# esp32-nbiot-xx-v12-wroom32.net
KiCad netlist of a schematic drawn in EAGLE
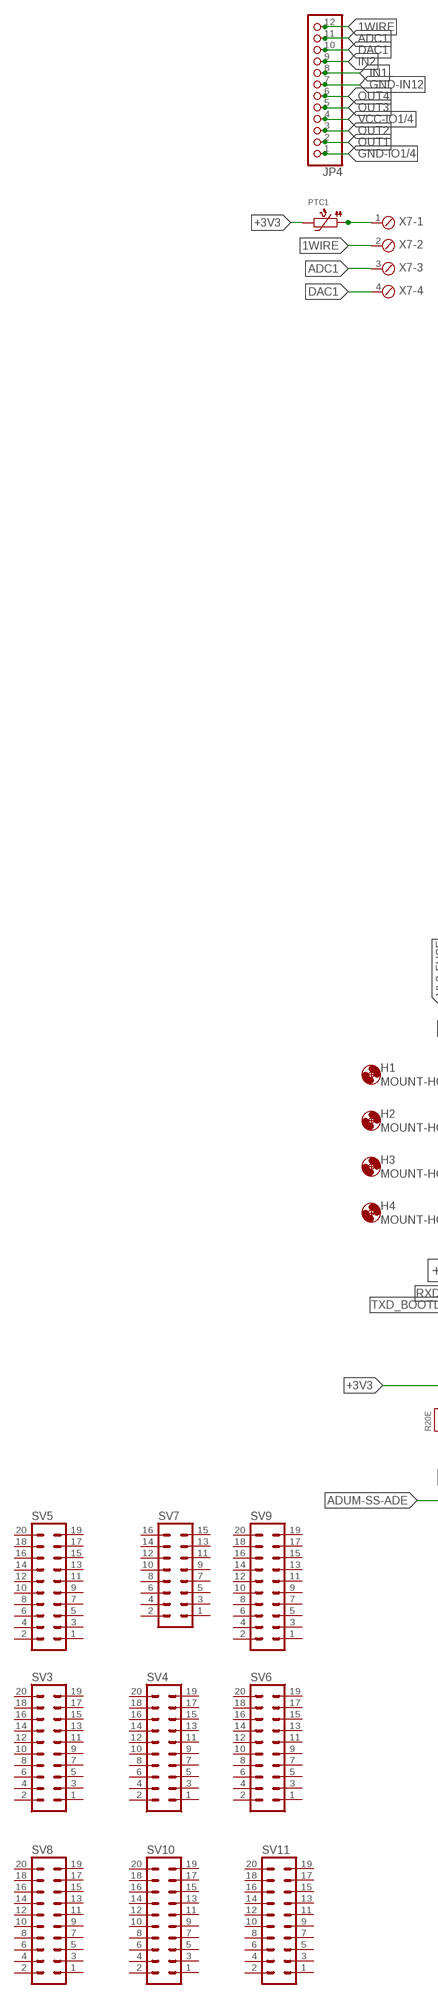
[diagram p0: schematic, sheet 1, part 1 of 3]
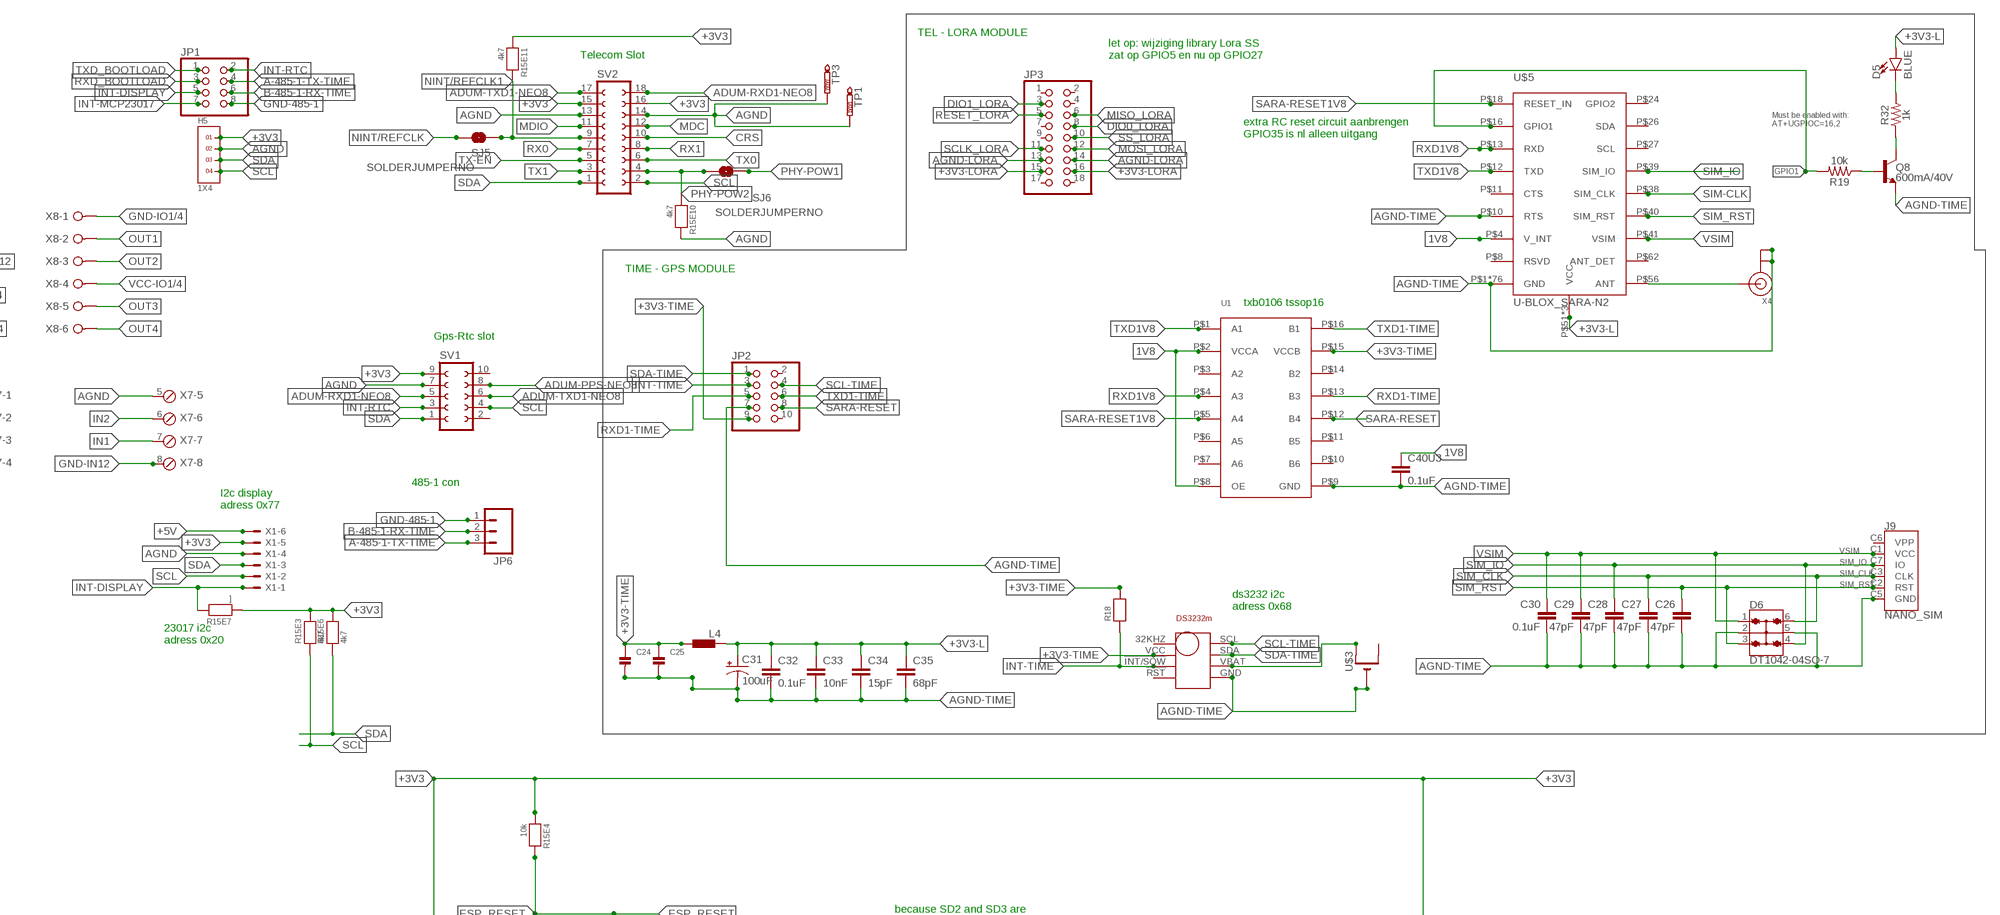
[diagram p1: schematic, sheet 1, part 2 of 3]
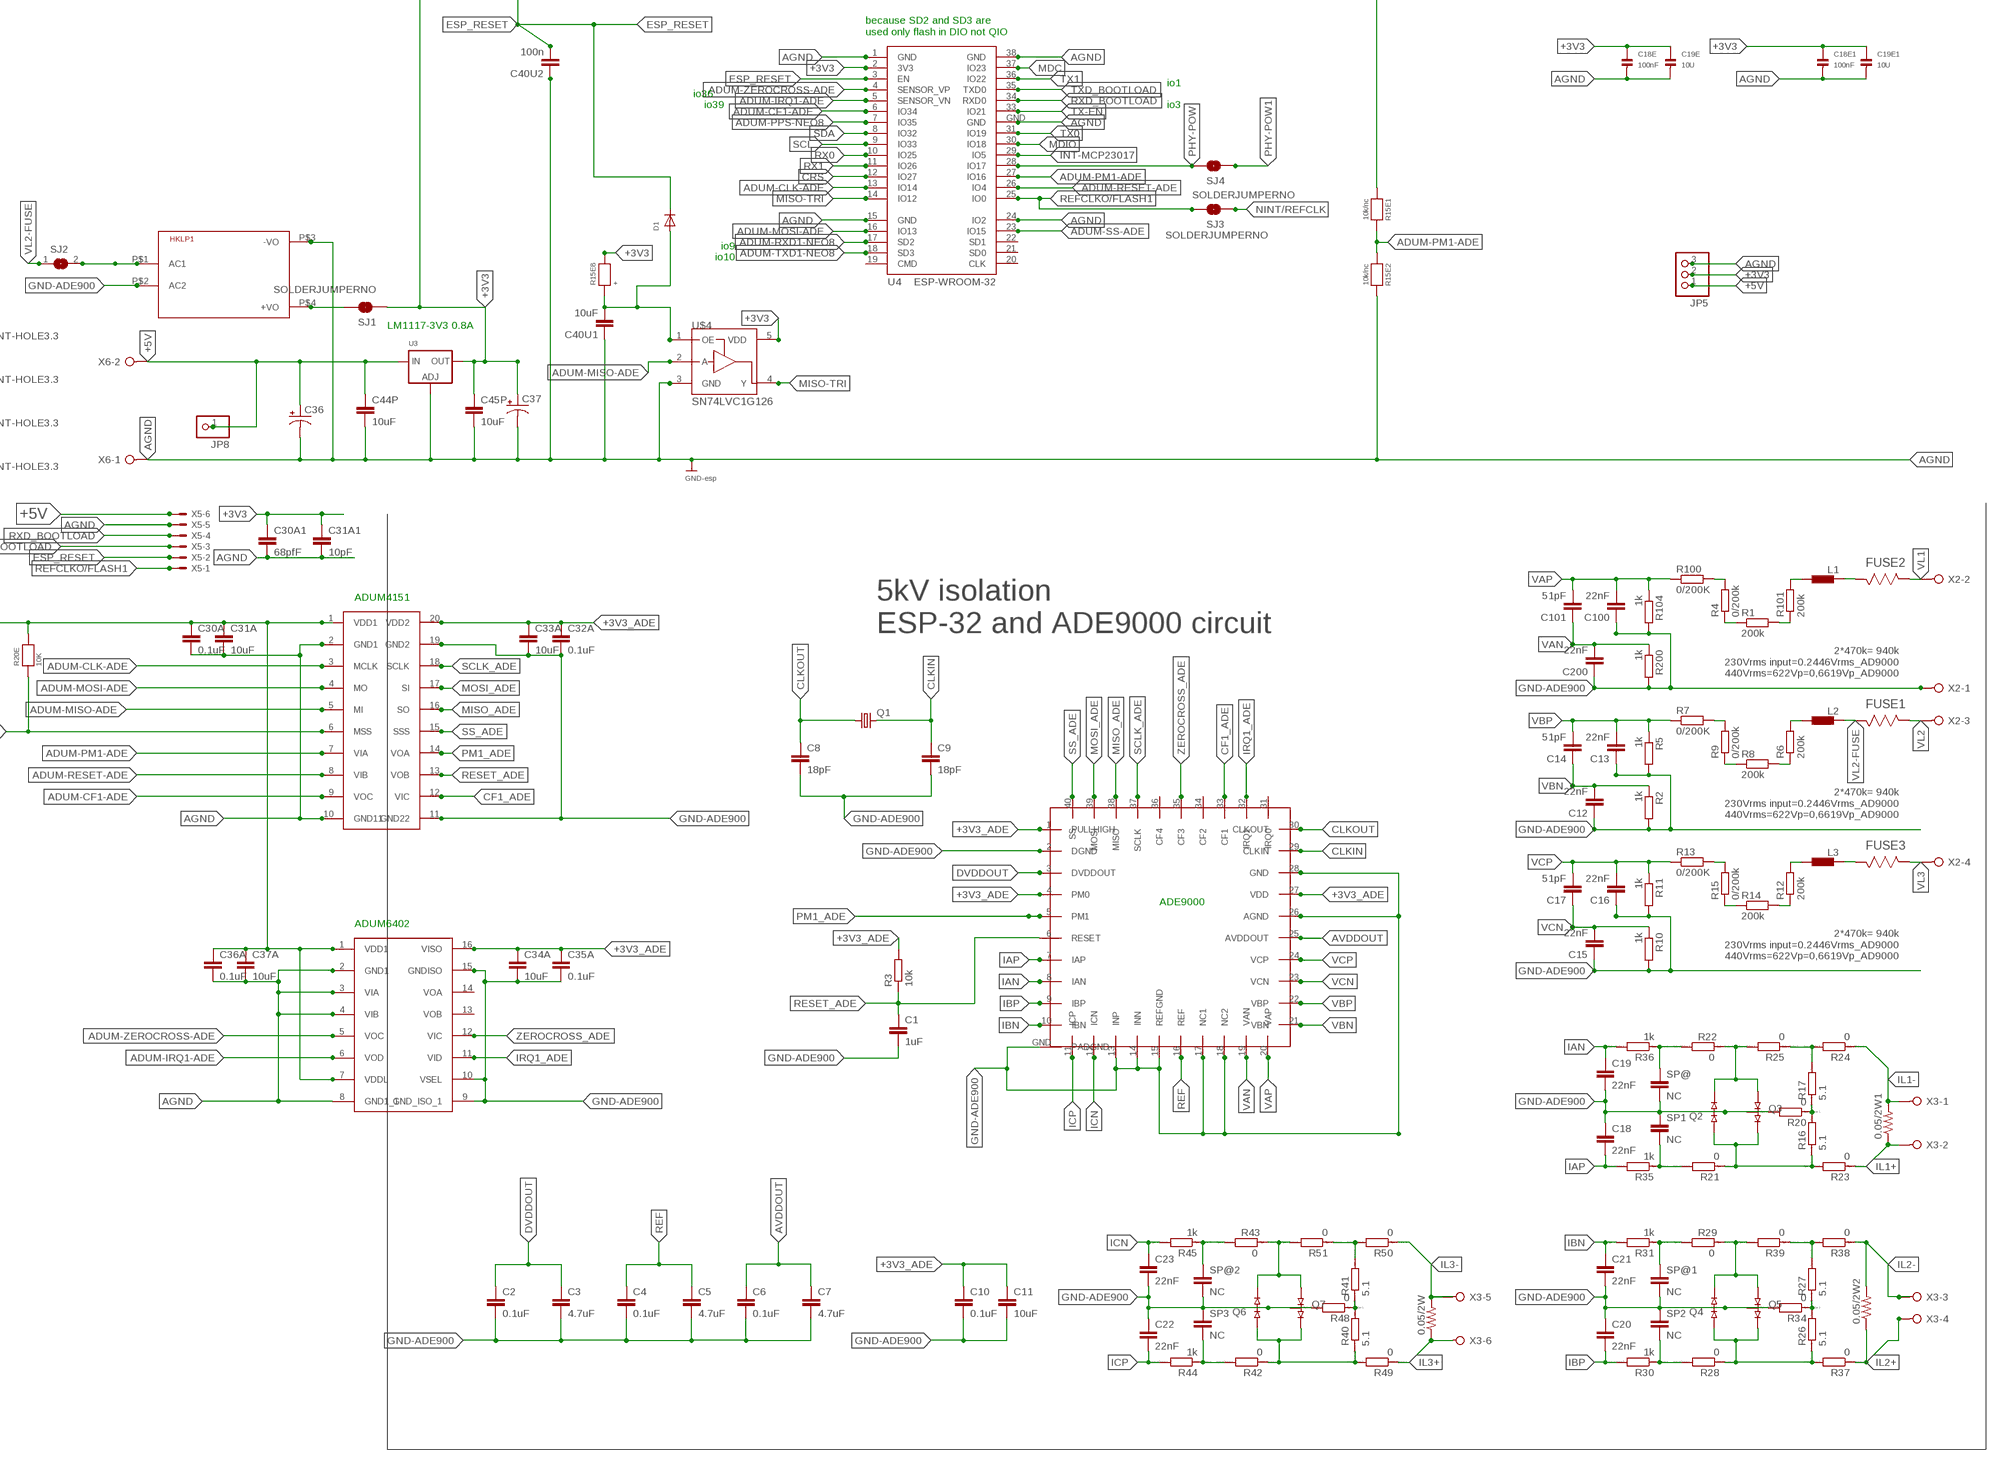
[diagram p2: schematic, sheet 1, part 3 of 3]

(export (version "E")
  (design (tool "Eeschema 10.0.6"))
  (components
    (comp (ref "0.05/2W")
      (value "R-US_R4527")
      (footprint "eagle-import:R4527")
      (libsource (lib "eagle-import") (part "R-US_R4527"))
    )
    (comp (ref "0.05/2W1")
      (value "R-US_R4527")
      (footprint "eagle-import:R4527")
      (libsource (lib "eagle-import") (part "R-US_R4527"))
    )
    (comp (ref "0.05/2W2")
      (value "R-US_R4527")
      (footprint "eagle-import:R4527")
      (libsource (lib "eagle-import") (part "R-US_R4527"))
    )
    (comp (ref "ADE9000")
      (value "ADE9000")
      (footprint "eagle-import:LFCSP40")
      (libsource (lib "eagle-import") (part "ADE9000"))
    )
    (comp (ref "ADUM4151")
      (value "ADUM4151")
      (footprint "eagle-import:SOIC20R")
      (libsource (lib "eagle-import") (part "ADUM4151"))
    )
    (comp (ref "ADUM6402-2")
      (value "ADUM6402")
      (footprint "eagle-import:SOIC16R")
      (libsource (lib "eagle-import") (part "ADUM6402"))
    )
    (comp (ref "C1")
      (value "1uF")
      (footprint "eagle-import:C0805")
      (libsource (lib "eagle-import") (part "C-EUC0805"))
    )
    (comp (ref "C2")
      (value "0.1uF")
      (footprint "eagle-import:C0805")
      (libsource (lib "eagle-import") (part "C-EUC0805"))
    )
    (comp (ref "C3")
      (value "4.7uF")
      (footprint "eagle-import:C0805")
      (libsource (lib "eagle-import") (part "C-EUC0805"))
    )
    (comp (ref "C4")
      (value "0.1uF")
      (footprint "eagle-import:C0805")
      (libsource (lib "eagle-import") (part "C-EUC0805"))
    )
    (comp (ref "C5")
      (value "4.7uF")
      (footprint "eagle-import:C0805")
      (libsource (lib "eagle-import") (part "C-EUC0805"))
    )
    (comp (ref "C6")
      (value "0.1uF")
      (footprint "eagle-import:C0805")
      (libsource (lib "eagle-import") (part "C-EUC0805"))
    )
    (comp (ref "C7")
      (value "4.7uF")
      (footprint "eagle-import:C0805")
      (libsource (lib "eagle-import") (part "C-EUC0805"))
    )
    (comp (ref "C8")
      (value "18pF")
      (footprint "eagle-import:C0805")
      (libsource (lib "eagle-import") (part "C-EUC0805"))
    )
    (comp (ref "C9")
      (value "18pF")
      (footprint "eagle-import:C0805")
      (libsource (lib "eagle-import") (part "C-EUC0805"))
    )
    (comp (ref "C10")
      (value "0.1uF")
      (footprint "eagle-import:C0805")
      (libsource (lib "eagle-import") (part "C-EUC0805"))
    )
    (comp (ref "C11")
      (value "10uF")
      (footprint "eagle-import:C0805")
      (libsource (lib "eagle-import") (part "C-EUC0805"))
    )
    (comp (ref "C12")
      (value "22nF")
      (footprint "eagle-import:C0805")
      (libsource (lib "eagle-import") (part "C-EUC0805"))
    )
    (comp (ref "C13")
      (value "22nF")
      (footprint "eagle-import:C0805")
      (libsource (lib "eagle-import") (part "C-EUC0805"))
    )
    (comp (ref "C14")
      (value "51pF")
      (footprint "eagle-import:C0805")
      (libsource (lib "eagle-import") (part "C-EUC0805"))
    )
    (comp (ref "C15")
      (value "22nF")
      (footprint "eagle-import:C0805")
      (libsource (lib "eagle-import") (part "C-EUC0805"))
    )
    (comp (ref "C16")
      (value "22nF")
      (footprint "eagle-import:C0805")
      (libsource (lib "eagle-import") (part "C-EUC0805"))
    )
    (comp (ref "C17")
      (value "51pF")
      (footprint "eagle-import:C0805")
      (libsource (lib "eagle-import") (part "C-EUC0805"))
    )
    (comp (ref "C18")
      (value "22nF")
      (footprint "eagle-import:C0805")
      (libsource (lib "eagle-import") (part "C-EUC0805"))
    )
    (comp (ref "C18E")
      (value "100nF")
      (footprint "eagle-import:_0805")
      (libsource (lib "eagle-import") (part "CAP_CERAMIC_0805"))
    )
    (comp (ref "C18E1")
      (value "100nF")
      (footprint "eagle-import:_0805")
      (libsource (lib "eagle-import") (part "CAP_CERAMIC_0805"))
    )
    (comp (ref "C19")
      (value "22nF")
      (footprint "eagle-import:C0805")
      (libsource (lib "eagle-import") (part "C-EUC0805"))
    )
    (comp (ref "C19E")
      (value "10U")
      (footprint "eagle-import:_0805")
      (libsource (lib "eagle-import") (part "CAP_CERAMIC_0805"))
    )
    (comp (ref "C19E1")
      (value "10U")
      (footprint "eagle-import:_0805")
      (libsource (lib "eagle-import") (part "CAP_CERAMIC_0805"))
    )
    (comp (ref "C20")
      (value "22nF")
      (footprint "eagle-import:C0805")
      (libsource (lib "eagle-import") (part "C-EUC0805"))
    )
    (comp (ref "C21")
      (value "22nF")
      (footprint "eagle-import:C0805")
      (libsource (lib "eagle-import") (part "C-EUC0805"))
    )
    (comp (ref "C22")
      (value "22nF")
      (footprint "eagle-import:C0805")
      (libsource (lib "eagle-import") (part "C-EUC0805"))
    )
    (comp (ref "C23")
      (value "22nF")
      (footprint "eagle-import:C0805")
      (libsource (lib "eagle-import") (part "C-EUC0805"))
    )
    (comp (ref "C24")
      (value "CAP_CERAMIC0805")
      (footprint "eagle-import:0805")
      (libsource (lib "eagle-import") (part "CAP_CERAMIC0805"))
    )
    (comp (ref "C25")
      (value "CAP_CERAMIC0805")
      (footprint "eagle-import:0805")
      (libsource (lib "eagle-import") (part "CAP_CERAMIC0805"))
    )
    (comp (ref "C26")
      (value "47pF")
      (footprint "eagle-import:0603")
      (libsource (lib "eagle-import") (part "47PF-0603-50V-5%"))
    )
    (comp (ref "C27")
      (value "47pF")
      (footprint "eagle-import:0603")
      (libsource (lib "eagle-import") (part "47PF-0603-50V-5%"))
    )
    (comp (ref "C28")
      (value "47pF")
      (footprint "eagle-import:0603")
      (libsource (lib "eagle-import") (part "47PF-0603-50V-5%"))
    )
    (comp (ref "C29")
      (value "47pF")
      (footprint "eagle-import:0603")
      (libsource (lib "eagle-import") (part "47PF-0603-50V-5%"))
    )
    (comp (ref "C30")
      (value "0.1uF")
      (footprint "eagle-import:0603")
      (libsource (lib "eagle-import") (part "0.1UF-0603-25V-(+80/-20%)"))
    )
    (comp (ref "C30A")
      (value "0.1uF")
      (footprint "eagle-import:C0805")
      (libsource (lib "eagle-import") (part "C-EUC0805"))
    )
    (comp (ref "C30A1")
      (value "68pfF")
      (footprint "eagle-import:C0805")
      (libsource (lib "eagle-import") (part "C-EUC0805"))
    )
    (comp (ref "C31")
      (value "100uF")
      (footprint "eagle-import:1206-POLAR")
      (libsource (lib "eagle-import") (part "100UF-POLAR-1206-6.3V-20%"))
    )
    (comp (ref "C31A")
      (value "10uF")
      (footprint "eagle-import:C0805")
      (libsource (lib "eagle-import") (part "C-EUC0805"))
    )
    (comp (ref "C31A1")
      (value "10pF")
      (footprint "eagle-import:C0805")
      (libsource (lib "eagle-import") (part "C-EUC0805"))
    )
    (comp (ref "C32")
      (value "0.1uF")
      (footprint "eagle-import:0603")
      (libsource (lib "eagle-import") (part "0.1UF-0603-25V-(+80/-20%)"))
    )
    (comp (ref "C32A")
      (value "0.1uF")
      (footprint "eagle-import:C0805")
      (libsource (lib "eagle-import") (part "C-EUC0805"))
    )
    (comp (ref "C33")
      (value "10nF")
      (footprint "eagle-import:0603")
      (libsource (lib "eagle-import") (part "10NF-0603-50V-10%"))
    )
    (comp (ref "C33A")
      (value "10uF")
      (footprint "eagle-import:C0805")
      (libsource (lib "eagle-import") (part "C-EUC0805"))
    )
    (comp (ref "C34")
      (value "15pF")
      (footprint "eagle-import:0603")
      (libsource (lib "eagle-import") (part "15PF-0603-50V-5%"))
    )
    (comp (ref "C34A")
      (value "10uF")
      (footprint "eagle-import:C0805")
      (libsource (lib "eagle-import") (part "C-EUC0805"))
    )
    (comp (ref "C35")
      (value "68pF")
      (footprint "eagle-import:0603")
      (libsource (lib "eagle-import") (part "68PF-0603-50V-5%"))
    )
    (comp (ref "C35A")
      (value "0.1uF")
      (footprint "eagle-import:C0805")
      (libsource (lib "eagle-import") (part "C-EUC0805"))
    )
    (comp (ref "C36")
      (value "CPOL-USD/7343-31R")
      (footprint "eagle-import:D_7343-31R")
      (libsource (lib "eagle-import") (part "CPOL-USD/7343-31R"))
    )
    (comp (ref "C36A")
      (value "0.1uF")
      (footprint "eagle-import:C0805")
      (libsource (lib "eagle-import") (part "C-EUC0805"))
    )
    (comp (ref "C37")
      (value "CPOL-USD/7343-31R")
      (footprint "eagle-import:D_7343-31R")
      (libsource (lib "eagle-import") (part "CPOL-USD/7343-31R"))
    )
    (comp (ref "C37A")
      (value "10uF")
      (footprint "eagle-import:C0805")
      (libsource (lib "eagle-import") (part "C-EUC0805"))
    )
    (comp (ref "C40U1")
      (value "10uF")
      (footprint "eagle-import:C0805")
      (libsource (lib "eagle-import") (part "C-EUC0805"))
    )
    (comp (ref "C40U2")
      (value "100n")
      (footprint "eagle-import:C0805")
      (libsource (lib "eagle-import") (part "C-EUC0805"))
    )
    (comp (ref "C40U3")
      (value "0.1uF")
      (footprint "eagle-import:C0805")
      (libsource (lib "eagle-import") (part "C-EUC0805"))
    )
    (comp (ref "C44P")
      (value "10uF")
      (footprint "eagle-import:C0805")
      (libsource (lib "eagle-import") (part "C-EUC0805"))
    )
    (comp (ref "C45P")
      (value "10uF")
      (footprint "eagle-import:C0805")
      (libsource (lib "eagle-import") (part "C-EUC0805"))
    )
    (comp (ref "C100")
      (value "22nF")
      (footprint "eagle-import:C0805")
      (libsource (lib "eagle-import") (part "C-EUC0805"))
    )
    (comp (ref "C101")
      (value "51pF")
      (footprint "eagle-import:C0805")
      (libsource (lib "eagle-import") (part "C-EUC0805"))
    )
    (comp (ref "C200")
      (value "22nF")
      (footprint "eagle-import:C0805")
      (libsource (lib "eagle-import") (part "C-EUC0805"))
    )
    (comp (ref "D1")
      (value "DIODE_SOD-123FL")
      (footprint "eagle-import:SOD-123FL")
      (libsource (lib "eagle-import") (part "DIODE_SOD-123FL"))
    )
    (comp (ref "D5")
      (value "BLUE")
      (footprint "eagle-import:LED-0603")
      (libsource (lib "eagle-import") (part "LED-BLUE0603"))
    )
    (comp (ref "D6")
      (value "DT1042-04SO-7")
      (footprint "eagle-import:SOT23-6L")
      (libsource (lib "eagle-import") (part "TVS_DIODE_ARRAY_4DT1042-04SO-7"))
    )
    (comp (ref "FUSE1")
      (value "CRCW25124R70JNEG")
      (footprint "eagle-import:RESC6332X71N")
      (fields (field (name "TOLERANCE") "±5%"))
      (libsource (lib "eagle-import") (part "CRCW25124R70JNEG"))
    )
    (comp (ref "FUSE2")
      (value "CRCW25124R70JNEG")
      (footprint "eagle-import:RESC6332X71N")
      (fields (field (name "TOLERANCE") "±5%"))
      (libsource (lib "eagle-import") (part "CRCW25124R70JNEG"))
    )
    (comp (ref "FUSE3")
      (value "CRCW25124R70JNEG")
      (footprint "eagle-import:RESC6332X71N")
      (fields (field (name "TOLERANCE") "±5%"))
      (libsource (lib "eagle-import") (part "CRCW25124R70JNEG"))
    )
    (comp (ref "H1")
      (value "MOUNT-HOLE3.3")
      (footprint "eagle-import:3,3")
      (libsource (lib "eagle-import") (part "MOUNT-HOLE3.3"))
    )
    (comp (ref "H2")
      (value "MOUNT-HOLE3.3")
      (footprint "eagle-import:3,3")
      (libsource (lib "eagle-import") (part "MOUNT-HOLE3.3"))
    )
    (comp (ref "H3")
      (value "MOUNT-HOLE3.3")
      (footprint "eagle-import:3,3")
      (libsource (lib "eagle-import") (part "MOUNT-HOLE3.3"))
    )
    (comp (ref "H4")
      (value "MOUNT-HOLE3.3")
      (footprint "eagle-import:3,3")
      (libsource (lib "eagle-import") (part "MOUNT-HOLE3.3"))
    )
    (comp (ref "H5")
      (value "1X4")
      (footprint "eagle-import:1X4")
      (libsource (lib "eagle-import") (part "1X4"))
    )
    (comp (ref "HKLP1")
      (value "HKLPM01")
      (footprint "eagle-import:HKLPM01")
      (libsource (lib "eagle-import") (part "HKLPM01"))
    )
    (comp (ref "J9")
      (value "NANO_SIM")
      (footprint "eagle-import:NANO_SIM_WURTH_693043020611")
      (libsource (lib "eagle-import") (part "NANO_SIMWURTH"))
    )
    (comp (ref "JP1")
      (value "PINHD-2X4")
      (footprint "eagle-import:2X04")
      (libsource (lib "eagle-import") (part "PINHD-2X4"))
    )
    (comp (ref "JP2")
      (value "PINHD-2X5/90")
      (footprint "eagle-import:2X05_90")
      (libsource (lib "eagle-import") (part "PINHD-2X5/90"))
    )
    (comp (ref "JP3")
      (value "PINHD-2X9/90")
      (footprint "eagle-import:2X09_90")
      (libsource (lib "eagle-import") (part "PINHD-2X9/90"))
    )
    (comp (ref "JP4")
      (value "PINHD-1X12")
      (footprint "eagle-import:1X12")
      (libsource (lib "eagle-import") (part "PINHD-1X12"))
    )
    (comp (ref "JP5")
      (value "PINHD-1X3")
      (footprint "eagle-import:1X03")
      (libsource (lib "eagle-import") (part "PINHD-1X3"))
    )
    (comp (ref "JP6")
      (value "M03SCREW")
      (footprint "eagle-import:SCREWTERMINAL-3.5MM-3")
      (libsource (lib "eagle-import") (part "M03SCREW"))
    )
    (comp (ref "JP8")
      (value "PINHD-1X1")
      (footprint "eagle-import:1X01")
      (libsource (lib "eagle-import") (part "PINHD-1X1"))
    )
    (comp (ref "L1")
      (value "1500")
      (footprint "eagle-import:M0805")
      (libsource (lib "eagle-import") (part "FERRITE_BEAD0805"))
    )
    (comp (ref "L2")
      (value "1500")
      (footprint "eagle-import:M0805")
      (libsource (lib "eagle-import") (part "FERRITE_BEAD0805"))
    )
    (comp (ref "L3")
      (value "1500")
      (footprint "eagle-import:M0805")
      (libsource (lib "eagle-import") (part "FERRITE_BEAD0805"))
    )
    (comp (ref "L4")
      (value "1500")
      (footprint "eagle-import:M0805")
      (libsource (lib "eagle-import") (part "FERRITE_BEAD0805"))
    )
    (comp (ref "PTC1")
      (value "PTC1206")
      (footprint "eagle-import:1206")
      (libsource (lib "eagle-import") (part "PTC1206"))
    )
    (comp (ref "Q1")
      (value "CRYSTALCTS406")
      (footprint "eagle-import:CTS406")
      (libsource (lib "eagle-import") (part "CRYSTALCTS406"))
    )
    (comp (ref "Q2")
      (value "MMBD4148SE")
      (footprint "eagle-import:SOT23-3")
      (libsource (lib "eagle-import") (part "DUAL_DIODE_SOT23-3"))
    )
    (comp (ref "Q3")
      (value "MMBD4148SE")
      (footprint "eagle-import:SOT23-3")
      (libsource (lib "eagle-import") (part "DUAL_DIODE_SOT23-3"))
    )
    (comp (ref "Q4")
      (value "MMBD4148SE")
      (footprint "eagle-import:SOT23-3")
      (libsource (lib "eagle-import") (part "DUAL_DIODE_SOT23-3"))
    )
    (comp (ref "Q5")
      (value "MMBD4148SE")
      (footprint "eagle-import:SOT23-3")
      (libsource (lib "eagle-import") (part "DUAL_DIODE_SOT23-3"))
    )
    (comp (ref "Q6")
      (value "MMBD4148SE")
      (footprint "eagle-import:SOT23-3")
      (libsource (lib "eagle-import") (part "DUAL_DIODE_SOT23-3"))
    )
    (comp (ref "Q7")
      (value "MMBD4148SE")
      (footprint "eagle-import:SOT23-3")
      (libsource (lib "eagle-import") (part "DUAL_DIODE_SOT23-3"))
    )
    (comp (ref "Q8")
      (value "600mA/40V")
      (footprint "eagle-import:SOT23-3")
      (libsource (lib "eagle-import") (part "TRANS_NPN-MMBT2222AL"))
    )
    (comp (ref "R1")
      (value "200k")
      (footprint "eagle-import:M1206")
      (libsource (lib "eagle-import") (part "R-EU_M1206"))
    )
    (comp (ref "R2")
      (value "1k")
      (footprint "eagle-import:M0805")
      (libsource (lib "eagle-import") (part "R-EU_M0805"))
    )
    (comp (ref "R3")
      (value "10k")
      (footprint "eagle-import:M0805")
      (libsource (lib "eagle-import") (part "R-EU_M0805"))
    )
    (comp (ref "R4")
      (value "0/200k")
      (footprint "eagle-import:M1206")
      (libsource (lib "eagle-import") (part "R-EU_M1206"))
    )
    (comp (ref "R5")
      (value "1k")
      (footprint "eagle-import:M0805")
      (libsource (lib "eagle-import") (part "R-EU_M0805"))
    )
    (comp (ref "R6")
      (value "200k")
      (footprint "eagle-import:M1206")
      (libsource (lib "eagle-import") (part "R-EU_M1206"))
    )
    (comp (ref "R7")
      (value "0/200K")
      (footprint "eagle-import:M1206")
      (libsource (lib "eagle-import") (part "R-EU_M1206"))
    )
    (comp (ref "R8")
      (value "200k")
      (footprint "eagle-import:M1206")
      (libsource (lib "eagle-import") (part "R-EU_M1206"))
    )
    (comp (ref "R9")
      (value "0/200k")
      (footprint "eagle-import:M1206")
      (libsource (lib "eagle-import") (part "R-EU_M1206"))
    )
    (comp (ref "R10")
      (value "1k")
      (footprint "eagle-import:M0805")
      (libsource (lib "eagle-import") (part "R-EU_M0805"))
    )
    (comp (ref "R11")
      (value "1k")
      (footprint "eagle-import:M0805")
      (libsource (lib "eagle-import") (part "R-EU_M0805"))
    )
    (comp (ref "R12")
      (value "200k")
      (footprint "eagle-import:M1206")
      (libsource (lib "eagle-import") (part "R-EU_M1206"))
    )
    (comp (ref "R13")
      (value "0/200K")
      (footprint "eagle-import:M1206")
      (libsource (lib "eagle-import") (part "R-EU_M1206"))
    )
    (comp (ref "R14")
      (value "200k")
      (footprint "eagle-import:M1206")
      (libsource (lib "eagle-import") (part "R-EU_M1206"))
    )
    (comp (ref "R15")
      (value "0/200k")
      (footprint "eagle-import:M1206")
      (libsource (lib "eagle-import") (part "R-EU_M1206"))
    )
    (comp (ref "R15E1")
      (value "10k/nc")
      (footprint "eagle-import:_0805")
      (libsource (lib "eagle-import") (part "RESISTOR_0805"))
    )
    (comp (ref "R15E2")
      (value "10k/nc")
      (footprint "eagle-import:_0805")
      (libsource (lib "eagle-import") (part "RESISTOR_0805"))
    )
    (comp (ref "R15E3")
      (value "4k7")
      (footprint "eagle-import:_0805")
      (libsource (lib "eagle-import") (part "RESISTOR_0805"))
    )
    (comp (ref "R15E4")
      (value "10k")
      (footprint "eagle-import:_0805")
      (libsource (lib "eagle-import") (part "RESISTOR_0805"))
    )
    (comp (ref "R15E6")
      (value "4k7")
      (footprint "eagle-import:_0805")
      (libsource (lib "eagle-import") (part "RESISTOR_0805"))
    )
    (comp (ref "R15E7")
      (value "]")
      (footprint "eagle-import:_0805")
      (libsource (lib "eagle-import") (part "RESISTOR_0805"))
    )
    (comp (ref "R15E8")
      (value "+")
      (footprint "eagle-import:_0805")
      (libsource (lib "eagle-import") (part "RESISTOR_0805"))
    )
    (comp (ref "R15E10")
      (value "4k7")
      (footprint "eagle-import:_0805")
      (libsource (lib "eagle-import") (part "RESISTOR_0805"))
    )
    (comp (ref "R15E11")
      (value "4k7")
      (footprint "eagle-import:_0805")
      (libsource (lib "eagle-import") (part "RESISTOR_0805"))
    )
    (comp (ref "R16")
      (value "5.1")
      (footprint "eagle-import:R0805")
      (description "RES, 5.1, 0W1, 0%1, 0805-SMT, ROHS")
      (fields (field (name "MANUFACTURER") " TE Connectivity Passive Product"))
      (libsource (lib "eagle-import") (part "R"))
    )
    (comp (ref "R17")
      (value "5.1")
      (footprint "eagle-import:R0805")
      (libsource (lib "eagle-import") (part "R"))
    )
    (comp (ref "R18")
      (value "RESISTOR0805")
      (footprint "eagle-import:0805")
      (libsource (lib "eagle-import") (part "RESISTOR0805"))
    )
    (comp (ref "R19")
      (value "10k")
      (footprint "eagle-import:0603")
      (libsource (lib "eagle-import") (part "10KOHM-0603-1/10W-1%"))
    )
    (comp (ref "R20")
      (value "0")
      (footprint "eagle-import:R0603")
      (libsource (lib "eagle-import") (part "RR0603"))
    )
    (comp (ref "R20E")
      (value "10K")
      (footprint "eagle-import:_0805")
      (libsource (lib "eagle-import") (part "RESISTOR_0805"))
    )
    (comp (ref "R21")
      (value "0")
      (footprint "eagle-import:R0603")
      (libsource (lib "eagle-import") (part "RR0603"))
    )
    (comp (ref "R22")
      (value "0")
      (footprint "eagle-import:R0603")
      (libsource (lib "eagle-import") (part "RR0603"))
    )
    (comp (ref "R23")
      (value "0")
      (footprint "eagle-import:R0603")
      (libsource (lib "eagle-import") (part "RR0603"))
    )
    (comp (ref "R24")
      (value "0")
      (footprint "eagle-import:R0603")
      (libsource (lib "eagle-import") (part "RR0603"))
    )
    (comp (ref "R25")
      (value "0")
      (footprint "eagle-import:R0603")
      (libsource (lib "eagle-import") (part "RR0603"))
    )
    (comp (ref "R26")
      (value "5.1")
      (footprint "eagle-import:R0805")
      (description "RES, 5.1, 0W1, 0%1, 0805-SMT, ROHS")
      (fields (field (name "MANUFACTURER") " TE Connectivity Passive Product"))
      (libsource (lib "eagle-import") (part "R"))
    )
    (comp (ref "R27")
      (value "5.1")
      (footprint "eagle-import:R0805")
      (libsource (lib "eagle-import") (part "R"))
    )
    (comp (ref "R28")
      (value "0")
      (footprint "eagle-import:R0603")
      (libsource (lib "eagle-import") (part "RR0603"))
    )
    (comp (ref "R29")
      (value "0")
      (footprint "eagle-import:R0603")
      (libsource (lib "eagle-import") (part "RR0603"))
    )
    (comp (ref "R30")
      (value "1k")
      (footprint "eagle-import:R0603")
      (libsource (lib "eagle-import") (part "RR0603"))
    )
    (comp (ref "R31")
      (value "1k")
      (footprint "eagle-import:R0603")
      (libsource (lib "eagle-import") (part "RR0603"))
    )
    (comp (ref "R32")
      (value "1k")
      (footprint "eagle-import:0603")
      (libsource (lib "eagle-import") (part "1KOHM-0603-1/10W-1%"))
    )
    (comp (ref "R34")
      (value "0")
      (footprint "eagle-import:R0603")
      (libsource (lib "eagle-import") (part "RR0603"))
    )
    (comp (ref "R35")
      (value "1k")
      (footprint "eagle-import:R0603")
      (libsource (lib "eagle-import") (part "RR0603"))
    )
    (comp (ref "R36")
      (value "1k")
      (footprint "eagle-import:R0603")
      (libsource (lib "eagle-import") (part "RR0603"))
    )
    (comp (ref "R37")
      (value "0")
      (footprint "eagle-import:R0603")
      (libsource (lib "eagle-import") (part "RR0603"))
    )
    (comp (ref "R38")
      (value "0")
      (footprint "eagle-import:R0603")
      (libsource (lib "eagle-import") (part "RR0603"))
    )
    (comp (ref "R39")
      (value "0")
      (footprint "eagle-import:R0603")
      (libsource (lib "eagle-import") (part "RR0603"))
    )
    (comp (ref "R40")
      (value "5.1")
      (footprint "eagle-import:R0805")
      (description "RES, 5.1, 0W1, 0%1, 0805-SMT, ROHS")
      (fields (field (name "MANUFACTURER") " TE Connectivity Passive Product"))
      (libsource (lib "eagle-import") (part "R"))
    )
    (comp (ref "R41")
      (value "5.1")
      (footprint "eagle-import:R0805")
      (libsource (lib "eagle-import") (part "R"))
    )
    (comp (ref "R42")
      (value "0")
      (footprint "eagle-import:R0603")
      (libsource (lib "eagle-import") (part "RR0603"))
    )
    (comp (ref "R43")
      (value "0")
      (footprint "eagle-import:R0603")
      (libsource (lib "eagle-import") (part "RR0603"))
    )
    (comp (ref "R44")
      (value "1k")
      (footprint "eagle-import:R0603")
      (libsource (lib "eagle-import") (part "RR0603"))
    )
    (comp (ref "R45")
      (value "1k")
      (footprint "eagle-import:R0603")
      (libsource (lib "eagle-import") (part "RR0603"))
    )
    (comp (ref "R48")
      (value "0")
      (footprint "eagle-import:R0603")
      (libsource (lib "eagle-import") (part "RR0603"))
    )
    (comp (ref "R49")
      (value "0")
      (footprint "eagle-import:R0603")
      (libsource (lib "eagle-import") (part "RR0603"))
    )
    (comp (ref "R50")
      (value "0")
      (footprint "eagle-import:R0603")
      (libsource (lib "eagle-import") (part "RR0603"))
    )
    (comp (ref "R51")
      (value "0")
      (footprint "eagle-import:R0603")
      (libsource (lib "eagle-import") (part "RR0603"))
    )
    (comp (ref "R100")
      (value "0/200K")
      (footprint "eagle-import:M1206")
      (libsource (lib "eagle-import") (part "R-EU_M1206"))
    )
    (comp (ref "R101")
      (value "200k")
      (footprint "eagle-import:M1206")
      (libsource (lib "eagle-import") (part "R-EU_M1206"))
    )
    (comp (ref "R104")
      (value "1k")
      (footprint "eagle-import:M0805")
      (libsource (lib "eagle-import") (part "R-EU_M0805"))
    )
    (comp (ref "R200")
      (value "1k")
      (footprint "eagle-import:M0805")
      (libsource (lib "eagle-import") (part "R-EU_M0805"))
    )
    (comp (ref "SJ1")
      (value "SOLDERJUMPERNO")
      (footprint "eagle-import:SJ_2S-NO")
      (libsource (lib "eagle-import") (part "SOLDERJUMPERNO"))
    )
    (comp (ref "SJ2")
      (value "SOLDERJUMPERWAVE")
      (footprint "eagle-import:SOLDERJUMPER_WAVE")
      (libsource (lib "eagle-import") (part "SOLDERJUMPERWAVE"))
    )
    (comp (ref "SJ3")
      (value "SOLDERJUMPERNO")
      (footprint "eagle-import:SJ_2S-NO")
      (libsource (lib "eagle-import") (part "SOLDERJUMPERNO"))
    )
    (comp (ref "SJ4")
      (value "SOLDERJUMPERNO")
      (footprint "eagle-import:SJ_2S-NO")
      (libsource (lib "eagle-import") (part "SOLDERJUMPERNO"))
    )
    (comp (ref "SJ5")
      (value "SOLDERJUMPERNO")
      (footprint "eagle-import:SJ_2S-NO")
      (libsource (lib "eagle-import") (part "SOLDERJUMPERNO"))
    )
    (comp (ref "SJ6")
      (value "SOLDERJUMPERNO")
      (footprint "eagle-import:SJ_2S-NO")
      (libsource (lib "eagle-import") (part "SOLDERJUMPERNO"))
    )
    (comp (ref "SP1")
      (value "NC")
      (footprint "eagle-import:C0805")
      (libsource (lib "eagle-import") (part "C-EUC0805"))
    )
    (comp (ref "SP2")
      (value "NC")
      (footprint "eagle-import:C0805")
      (libsource (lib "eagle-import") (part "C-EUC0805"))
    )
    (comp (ref "SP3")
      (value "NC")
      (footprint "eagle-import:C0805")
      (libsource (lib "eagle-import") (part "C-EUC0805"))
    )
    (comp (ref "SP@")
      (value "NC")
      (footprint "eagle-import:C0805")
      (libsource (lib "eagle-import") (part "C-EUC0805"))
    )
    (comp (ref "SP@1")
      (value "NC")
      (footprint "eagle-import:C0805")
      (libsource (lib "eagle-import") (part "C-EUC0805"))
    )
    (comp (ref "SP@2")
      (value "NC")
      (footprint "eagle-import:C0805")
      (libsource (lib "eagle-import") (part "C-EUC0805"))
    )
    (comp (ref "SV1")
      (value "FE05-2W")
      (footprint "eagle-import:FE05-2W")
      (libsource (lib "eagle-import") (part "FE05-2W"))
    )
    (comp (ref "SV2")
      (value "FE09-2W")
      (footprint "eagle-import:FE09-2W")
      (libsource (lib "eagle-import") (part "FE09-2W"))
    )
    (comp (ref "SV3")
      (value "MA10-2")
      (footprint "eagle-import:MA10-2")
      (libsource (lib "eagle-import") (part "MA10-2"))
    )
    (comp (ref "SV4")
      (value "MA10-2")
      (footprint "eagle-import:MA10-2")
      (libsource (lib "eagle-import") (part "MA10-2"))
    )
    (comp (ref "SV5")
      (value "MA10-2")
      (footprint "eagle-import:MA10-2")
      (libsource (lib "eagle-import") (part "MA10-2"))
    )
    (comp (ref "SV6")
      (value "MA10-2")
      (footprint "eagle-import:MA10-2")
      (libsource (lib "eagle-import") (part "MA10-2"))
    )
    (comp (ref "SV7")
      (value "MA08-2")
      (footprint "eagle-import:MA08-2")
      (libsource (lib "eagle-import") (part "MA08-2"))
    )
    (comp (ref "SV8")
      (value "MA10-2")
      (footprint "eagle-import:MA10-2")
      (libsource (lib "eagle-import") (part "MA10-2"))
    )
    (comp (ref "SV9")
      (value "MA10-2")
      (footprint "eagle-import:MA10-2")
      (libsource (lib "eagle-import") (part "MA10-2"))
    )
    (comp (ref "SV10")
      (value "MA10-2")
      (footprint "eagle-import:MA10-2")
      (libsource (lib "eagle-import") (part "MA10-2"))
    )
    (comp (ref "SV11")
      (value "MA10-2")
      (footprint "eagle-import:MA10-2")
      (libsource (lib "eagle-import") (part "MA10-2"))
    )
    (comp (ref "TP1")
      (value "PTR1TP08SQ")
      (footprint "eagle-import:TP08SQ")
      (libsource (lib "eagle-import") (part "PTR1TP08SQ"))
    )
    (comp (ref "TP3")
      (value "PTR1TP08SQ")
      (footprint "eagle-import:TP08SQ")
      (libsource (lib "eagle-import") (part "PTR1TP08SQ"))
    )
    (comp (ref "U$1")
      (value "DS3232M")
      (footprint "eagle-import:SOIC8")
      (libsource (lib "eagle-import") (part "DS3232M"))
    )
    (comp (ref "U$3")
      (value "CR1220SMT")
      (footprint "eagle-import:CR1220-SMD")
      (libsource (lib "eagle-import") (part "CR1220SMT"))
    )
    (comp (ref "U$4")
      (value "SN74LVC1G126DBVT")
      (footprint "eagle-import:SOT-23-5L")
      (fields (field (name "MF") "Texas Instruments"))
      (libsource (lib "eagle-import") (part "SN74LVC1G126DBVT"))
    )
    (comp (ref "U$5")
      (value "U-BLOX_SARA-N2")
      (footprint "eagle-import:SARA-N2")
      (libsource (lib "eagle-import") (part "U-BLOX_SARA-N2"))
    )
    (comp (ref "U1")
      (value "TXB0106")
      (footprint "eagle-import:TSSOP16")
      (fields (field (name "MF") "Texas Instruments"))
      (libsource (lib "eagle-import") (part "TXB0106"))
    )
    (comp (ref "U3")
      (value "LM1117SOT223-REFLOW")
      (footprint "eagle-import:SOT223-R")
      (libsource (lib "eagle-import") (part "LM1117SOT223-REFLOW"))
    )
    (comp (ref "U4")
      (value "ESP-WROOM-32")
      (footprint "eagle-import:ESP-WROOM-32")
      (libsource (lib "eagle-import") (part "ESP-WROOM-32"))
    )
    (comp (ref "X1")
      (value "22-23-2061")
      (footprint "eagle-import:22-23-2061")
      (fields (field (name "MF") "MOLEX"))
      (libsource (lib "eagle-import") (part "22-23-2061"))
    )
    (comp (ref "X2")
      (value "W237-04P")
      (footprint "eagle-import:W237-4P")
      (libsource (lib "eagle-import") (part "W237-04P"))
    )
    (comp (ref "X3")
      (value "W237-06P")
      (footprint "eagle-import:W237-6P")
      (libsource (lib "eagle-import") (part "W237-06P"))
    )
    (comp (ref "X4")
      (value "ANTENNA_U.FL")
      (footprint "eagle-import:U.FL")
      (libsource (lib "eagle-import") (part "ANTENNA_U.FL"))
    )
    (comp (ref "X5")
      (value "22-23-2061")
      (footprint "eagle-import:22-23-2061")
      (fields (field (name "MF") "MOLEX"))
      (libsource (lib "eagle-import") (part "22-23-2061"))
    )
    (comp (ref "X6")
      (value "W237-02P")
      (footprint "eagle-import:W237-132")
      (libsource (lib "eagle-import") (part "W237-02P"))
    )
    (comp (ref "X7")
      (value "MPT8")
      (footprint "eagle-import:8POL254")
      (libsource (lib "eagle-import") (part "MPT8"))
    )
    (comp (ref "X8")
      (value "W237-06P")
      (footprint "eagle-import:W237-6P")
      (libsource (lib "eagle-import") (part "W237-06P"))
    )
  )
  (nets
    (net (code "1") (name "+3V3") (class "Default")
      (node (ref "ADUM4151") (pin "1") (pinfunction "VDD1_1") (pintype "bidirectional"))
      (node (ref "ADUM6402-2") (pin "1") (pinfunction "VDD1_1") (pintype "bidirectional"))
      (node (ref "ADUM6402-2") (pin "7") (pinfunction "VDDL_7") (pintype "bidirectional"))
      (node (ref "C18E") (pin "1") (pinfunction "P$1_1") (pintype "passive"))
      (node (ref "C18E1") (pin "1") (pinfunction "P$1_1") (pintype "passive"))
      (node (ref "C19E") (pin "1") (pinfunction "P$1_1") (pintype "passive"))
      (node (ref "C19E1") (pin "1") (pinfunction "P$1_1") (pintype "passive"))
      (node (ref "C30A") (pin "1") (pinfunction "1_1") (pintype "passive"))
      (node (ref "C30A1") (pin "1") (pinfunction "1_1") (pintype "passive"))
      (node (ref "C31A") (pin "1") (pinfunction "1_1") (pintype "passive"))
      (node (ref "C31A1") (pin "1") (pinfunction "1_1") (pintype "passive"))
      (node (ref "C36A") (pin "1") (pinfunction "1_1") (pintype "passive"))
      (node (ref "C37") (pin "+") (pinfunction "+_+") (pintype "passive"))
      (node (ref "C37A") (pin "1") (pinfunction "1_1") (pintype "passive"))
      (node (ref "C45P") (pin "1") (pinfunction "1_1") (pintype "passive"))
      (node (ref "H5") (pin "1") (pinfunction "1_1") (pintype "bidirectional"))
      (node (ref "JP5") (pin "2") (pinfunction "2_2") (pintype "passive"))
      (node (ref "PTC1") (pin "2") (pinfunction "2_2") (pintype "passive"))
      (node (ref "R15E1") (pin "1") (pinfunction "1_1") (pintype "passive"))
      (node (ref "R15E11") (pin "1") (pinfunction "1_1") (pintype "passive"))
      (node (ref "R15E3") (pin "2") (pinfunction "2_2") (pintype "passive"))
      (node (ref "R15E4") (pin "1") (pinfunction "1_1") (pintype "passive"))
      (node (ref "R15E6") (pin "2") (pinfunction "2_2") (pintype "passive"))
      (node (ref "R15E7") (pin "1") (pinfunction "1_1") (pintype "passive"))
      (node (ref "R15E8") (pin "2") (pinfunction "2_2") (pintype "passive"))
      (node (ref "R20E") (pin "2") (pinfunction "2_2") (pintype "passive"))
      (node (ref "SJ1") (pin "1") (pinfunction "1_1") (pintype "passive"))
      (node (ref "SV1") (pin "9") (pinfunction "9_9") (pintype "passive"))
      (node (ref "SV2") (pin "15") (pinfunction "15_15") (pintype "passive"))
      (node (ref "SV2") (pin "16") (pinfunction "16_16") (pintype "passive"))
      (node (ref "U$4") (pin "5") (pinfunction "VDD_5") (pintype "bidirectional"))
      (node (ref "U3") (pin "2") (pinfunction "OUT_2") (pintype "passive"))
      (node (ref "U4") (pin "2") (pinfunction "3V3_2") (pintype "power_in"))
      (node (ref "X1") (pin "5") (pinfunction "S_5") (pintype "passive"))
    )
    (net (code "2") (name "+3V3-L") (class "Default")
      (node (ref "C31") (pin "1") (pinfunction "+_1") (pintype "passive"))
      (node (ref "C32") (pin "1") (pinfunction "1_1") (pintype "passive"))
      (node (ref "C33") (pin "1") (pinfunction "1_1") (pintype "passive"))
      (node (ref "C34") (pin "1") (pinfunction "1_1") (pintype "passive"))
      (node (ref "C35") (pin "1") (pinfunction "1_1") (pintype "passive"))
      (node (ref "D5") (pin "A") (pinfunction "A_A") (pintype "passive"))
      (node (ref "L4") (pin "1") (pinfunction "1_1") (pintype "passive"))
      (node (ref "U$5") (pin "P$51") (pinfunction "VCC_P$51") (pintype "power_in"))
      (node (ref "U$5") (pin "P$52") (pinfunction "VCC_P$52") (pintype "power_in"))
      (node (ref "U$5") (pin "P$53") (pinfunction "VCC_P$53") (pintype "power_in"))
    )
    (net (code "3") (name "+3V3-LORA") (class "Default")
      (node (ref "JP3") (pin "15") (pinfunction "15_15") (pintype "passive"))
      (node (ref "JP3") (pin "16") (pinfunction "16_16") (pintype "passive"))
    )
    (net (code "4") (name "+3V3-TIME") (class "Default")
      (node (ref "C24") (pin "1") (pinfunction "P$1_1") (pintype "passive"))
      (node (ref "C25") (pin "1") (pinfunction "P$1_1") (pintype "passive"))
      (node (ref "JP2") (pin "9") (pinfunction "9_9") (pintype "passive"))
      (node (ref "L4") (pin "2") (pinfunction "2_2") (pintype "passive"))
      (node (ref "R18") (pin "2") (pinfunction "2_2") (pintype "passive"))
      (node (ref "U$1") (pin "VCC") (pinfunction "VCC_VCC") (pintype "power_in"))
      (node (ref "U1") (pin "P$15") (pinfunction "VCCB_P$15") (pintype "bidirectional"))
    )
    (net (code "5") (name "+3V3_ADE") (class "Default")
      (node (ref "ADE9000") (pin "1") (pinfunction "PULLHIGH_1") (pintype "bidirectional"))
      (node (ref "ADE9000") (pin "27") (pinfunction "VDD_27") (pintype "bidirectional"))
      (node (ref "ADE9000") (pin "4") (pinfunction "PM0_4") (pintype "bidirectional"))
      (node (ref "ADUM4151") (pin "20") (pinfunction "VDD2_20") (pintype "bidirectional"))
      (node (ref "ADUM6402-2") (pin "16") (pinfunction "VISO_16") (pintype "bidirectional"))
      (node (ref "C10") (pin "1") (pinfunction "1_1") (pintype "passive"))
      (node (ref "C11") (pin "1") (pinfunction "1_1") (pintype "passive"))
      (node (ref "C32A") (pin "1") (pinfunction "1_1") (pintype "passive"))
      (node (ref "C33A") (pin "1") (pinfunction "1_1") (pintype "passive"))
      (node (ref "C34A") (pin "1") (pinfunction "1_1") (pintype "passive"))
      (node (ref "C35A") (pin "1") (pinfunction "1_1") (pintype "passive"))
      (node (ref "R3") (pin "2") (pinfunction "2_2") (pintype "passive"))
    )
    (net (code "6") (name "+5V") (class "Default")
      (node (ref "C36") (pin "+") (pinfunction "+_+") (pintype "passive"))
      (node (ref "C44P") (pin "1") (pinfunction "1_1") (pintype "passive"))
      (node (ref "JP5") (pin "1") (pinfunction "1_1") (pintype "passive"))
      (node (ref "JP8") (pin "1") (pinfunction "1_1") (pintype "passive"))
      (node (ref "U3") (pin "3") (pinfunction "IN_3") (pintype "input"))
      (node (ref "X1") (pin "6") (pinfunction "S_6") (pintype "passive"))
      (node (ref "X5") (pin "6") (pinfunction "S_6") (pintype "passive"))
      (node (ref "X6") (pin "2") (pinfunction "KL_2") (pintype "passive"))
    )
    (net (code "7") (name "1V8") (class "Default")
      (node (ref "C40U3") (pin "1") (pinfunction "1_1") (pintype "passive"))
      (node (ref "U$5") (pin "P$4") (pinfunction "V_INT_P$4") (pintype "bidirectional"))
      (node (ref "U1") (pin "P$2") (pinfunction "VCCA_P$2") (pintype "bidirectional"))
      (node (ref "U1") (pin "P$8") (pinfunction "OE_P$8") (pintype "bidirectional"))
    )
    (net (code "8") (name "1WIRE") (class "Default")
      (node (ref "JP4") (pin "12") (pinfunction "12_12") (pintype "passive"))
      (node (ref "X7") (pin "2") (pinfunction "1_2") (pintype "passive"))
    )
    (net (code "9") (name "A-485-1-TX-TIME") (class "Default")
      (node (ref "JP1") (pin "4") (pinfunction "4_4") (pintype "passive"))
      (node (ref "JP6") (pin "3") (pinfunction "3_3") (pintype "passive"))
    )
    (net (code "10") (name "ADC1") (class "Default")
      (node (ref "JP4") (pin "11") (pinfunction "11_11") (pintype "passive"))
      (node (ref "X7") (pin "3") (pinfunction "1_3") (pintype "passive"))
    )
    (net (code "11") (name "ADUM-CF1-ADE") (class "Default")
      (node (ref "ADUM4151") (pin "9") (pinfunction "VOC_9") (pintype "bidirectional"))
      (node (ref "U4") (pin "6") (pinfunction "IO34_6") (pintype "bidirectional"))
    )
    (net (code "12") (name "ADUM-CLK-ADE") (class "Default")
      (node (ref "ADUM4151") (pin "3") (pinfunction "MCLK_3") (pintype "bidirectional"))
      (node (ref "U4") (pin "13") (pinfunction "IO14_13") (pintype "bidirectional"))
    )
    (net (code "13") (name "ADUM-IRQ1-ADE") (class "Default")
      (node (ref "ADUM6402-2") (pin "6") (pinfunction "VOD_6") (pintype "bidirectional"))
      (node (ref "U4") (pin "5") (pinfunction "SENSOR_VN_5") (pintype "bidirectional"))
    )
    (net (code "14") (name "ADUM-MISO-ADE") (class "Default")
      (node (ref "ADUM4151") (pin "5") (pinfunction "MI_5") (pintype "bidirectional"))
      (node (ref "U$4") (pin "2") (pinfunction "A_2") (pintype "bidirectional"))
    )
    (net (code "15") (name "ADUM-MOSI-ADE") (class "Default")
      (node (ref "ADUM4151") (pin "4") (pinfunction "MO_4") (pintype "bidirectional"))
      (node (ref "U4") (pin "16") (pinfunction "IO13_16") (pintype "bidirectional"))
    )
    (net (code "16") (name "ADUM-PM1-ADE") (class "Default")
      (node (ref "ADUM4151") (pin "7") (pinfunction "VIA_7") (pintype "bidirectional"))
      (node (ref "R15E1") (pin "2") (pinfunction "2_2") (pintype "passive"))
      (node (ref "R15E2") (pin "1") (pinfunction "1_1") (pintype "passive"))
      (node (ref "U4") (pin "27") (pinfunction "IO16_27") (pintype "bidirectional"))
    )
    (net (code "17") (name "ADUM-PPS-NEO8") (class "Default")
      (node (ref "SV1") (pin "8") (pinfunction "8_8") (pintype "passive"))
      (node (ref "U4") (pin "7") (pinfunction "IO35_7") (pintype "bidirectional"))
    )
    (net (code "18") (name "ADUM-RESET-ADE") (class "Default")
      (node (ref "ADUM4151") (pin "8") (pinfunction "VIB_8") (pintype "bidirectional"))
      (node (ref "U4") (pin "26") (pinfunction "IO4_26") (pintype "bidirectional"))
    )
    (net (code "19") (name "ADUM-RXD1-NEO8") (class "Default")
      (node (ref "SV1") (pin "5") (pinfunction "5_5") (pintype "passive"))
      (node (ref "SV2") (pin "18") (pinfunction "18_18") (pintype "passive"))
      (node (ref "U4") (pin "17") (pinfunction "SD2_17") (pintype "bidirectional"))
    )
    (net (code "20") (name "ADUM-SS-ADE") (class "Default")
      (node (ref "ADUM4151") (pin "6") (pinfunction "MSS_6") (pintype "bidirectional"))
      (node (ref "R20E") (pin "1") (pinfunction "1_1") (pintype "passive"))
      (node (ref "U4") (pin "23") (pinfunction "IO15_23") (pintype "bidirectional"))
    )
    (net (code "21") (name "ADUM-TXD1-NEO8") (class "Default")
      (node (ref "SV1") (pin "6") (pinfunction "6_6") (pintype "passive"))
      (node (ref "SV2") (pin "17") (pinfunction "17_17") (pintype "passive"))
      (node (ref "U4") (pin "18") (pinfunction "SD3_18") (pintype "bidirectional"))
    )
    (net (code "22") (name "ADUM-ZEROCROSS-ADE") (class "Default")
      (node (ref "ADUM6402-2") (pin "5") (pinfunction "VOC_5") (pintype "bidirectional"))
      (node (ref "U4") (pin "4") (pinfunction "SENSOR_VP_4") (pintype "bidirectional"))
    )
    (net (code "23") (name "AGND") (class "Default")
      (node (ref "ADUM4151") (pin "10") (pinfunction "GND11_10") (pintype "bidirectional"))
      (node (ref "ADUM4151") (pin "2") (pinfunction "GND1_2") (pintype "bidirectional"))
      (node (ref "ADUM6402-2") (pin "2") (pinfunction "GND1_2") (pintype "bidirectional"))
      (node (ref "ADUM6402-2") (pin "3") (pinfunction "VIA_3") (pintype "bidirectional"))
      (node (ref "ADUM6402-2") (pin "4") (pinfunction "VIB_4") (pintype "bidirectional"))
      (node (ref "ADUM6402-2") (pin "8") (pinfunction "GND1_1_8") (pintype "bidirectional"))
      (node (ref "C18E") (pin "2") (pinfunction "P$2_2") (pintype "passive"))
      (node (ref "C18E1") (pin "2") (pinfunction "P$2_2") (pintype "passive"))
      (node (ref "C19E") (pin "2") (pinfunction "P$2_2") (pintype "passive"))
      (node (ref "C19E1") (pin "2") (pinfunction "P$2_2") (pintype "passive"))
      (node (ref "C30A") (pin "2") (pinfunction "2_2") (pintype "passive"))
      (node (ref "C30A1") (pin "2") (pinfunction "2_2") (pintype "passive"))
      (node (ref "C31A") (pin "2") (pinfunction "2_2") (pintype "passive"))
      (node (ref "C31A1") (pin "2") (pinfunction "2_2") (pintype "passive"))
      (node (ref "C36") (pin "-") (pinfunction "-_-") (pintype "passive"))
      (node (ref "C36A") (pin "2") (pinfunction "2_2") (pintype "passive"))
      (node (ref "C37") (pin "-") (pinfunction "-_-") (pintype "passive"))
      (node (ref "C37A") (pin "2") (pinfunction "2_2") (pintype "passive"))
      (node (ref "C40U1") (pin "1") (pinfunction "1_1") (pintype "passive"))
      (node (ref "C40U2") (pin "1") (pinfunction "1_1") (pintype "passive"))
      (node (ref "C44P") (pin "2") (pinfunction "2_2") (pintype "passive"))
      (node (ref "C45P") (pin "2") (pinfunction "2_2") (pintype "passive"))
      (node (ref "H5") (pin "2") (pinfunction "2_2") (pintype "bidirectional"))
      (node (ref "HKLP1") (pin "P$3") (pinfunction "-VO_P$3") (pintype "bidirectional"))
      (node (ref "JP5") (pin "3") (pinfunction "3_3") (pintype "passive"))
      (node (ref "R15E10") (pin "2") (pinfunction "2_2") (pintype "passive"))
      (node (ref "R15E2") (pin "2") (pinfunction "2_2") (pintype "passive"))
      (node (ref "SV1") (pin "7") (pinfunction "7_7") (pintype "passive"))
      (node (ref "SV2") (pin "13") (pinfunction "13_13") (pintype "passive"))
      (node (ref "SV2") (pin "14") (pinfunction "14_14") (pintype "passive"))
      (node (ref "TP1") (pin "TP") (pinfunction "TP_TP") (pintype "input"))
      (node (ref "TP3") (pin "TP") (pinfunction "TP_TP") (pintype "input"))
      (node (ref "U$4") (pin "3") (pinfunction "GND_3") (pintype "bidirectional"))
      (node (ref "U3") (pin "1") (pinfunction "ADJ_1") (pintype "input"))
      (node (ref "U4") (pin "1") (pinfunction "GND_1") (pintype "power_in"))
      (node (ref "U4") (pin "15") (pinfunction "GND_15") (pintype "power_in"))
      (node (ref "U4") (pin "24") (pinfunction "IO2_24") (pintype "bidirectional"))
      (node (ref "U4") (pin "38") (pinfunction "GND_38") (pintype "power_in"))
      (node (ref "U4") (pin "GND") (pinfunction "GND_GND") (pintype "power_in"))
      (node (ref "X1") (pin "4") (pinfunction "S_4") (pintype "passive"))
      (node (ref "X5") (pin "5") (pinfunction "S_5") (pintype "passive"))
      (node (ref "X6") (pin "1") (pinfunction "KL_1") (pintype "passive"))
      (node (ref "X7") (pin "5") (pinfunction "1_5") (pintype "passive"))
    )
    (net (code "24") (name "AGND-LORA") (class "Default")
      (node (ref "JP3") (pin "13") (pinfunction "13_13") (pintype "passive"))
      (node (ref "JP3") (pin "14") (pinfunction "14_14") (pintype "passive"))
    )
    (net (code "25") (name "AGND-TIME") (class "Default")
      (node (ref "C24") (pin "2") (pinfunction "P$2_2") (pintype "passive"))
      (node (ref "C25") (pin "2") (pinfunction "P$2_2") (pintype "passive"))
      (node (ref "C26") (pin "2") (pinfunction "2_2") (pintype "passive"))
      (node (ref "C27") (pin "2") (pinfunction "2_2") (pintype "passive"))
      (node (ref "C28") (pin "2") (pinfunction "2_2") (pintype "passive"))
      (node (ref "C29") (pin "2") (pinfunction "2_2") (pintype "passive"))
      (node (ref "C30") (pin "2") (pinfunction "2_2") (pintype "passive"))
      (node (ref "C31") (pin "2") (pinfunction "-_2") (pintype "passive"))
      (node (ref "C32") (pin "2") (pinfunction "2_2") (pintype "passive"))
      (node (ref "C33") (pin "2") (pinfunction "2_2") (pintype "passive"))
      (node (ref "C34") (pin "2") (pinfunction "2_2") (pintype "passive"))
      (node (ref "C35") (pin "2") (pinfunction "2_2") (pintype "passive"))
      (node (ref "C40U3") (pin "2") (pinfunction "2_2") (pintype "passive"))
      (node (ref "D6") (pin "2") (pinfunction "2_2") (pintype "bidirectional"))
      (node (ref "D6") (pin "5") (pinfunction "5_5") (pintype "bidirectional"))
      (node (ref "J9") (pin "C5") (pinfunction "GND_C5") (pintype "bidirectional"))
      (node (ref "JP2") (pin "7") (pinfunction "7_7") (pintype "passive"))
      (node (ref "Q8") (pin "2") (pinfunction "E_2") (pintype "passive"))
      (node (ref "U$1") (pin "GND") (pinfunction "GND_GND") (pintype "power_in"))
      (node (ref "U$3") (pin "-") (pinfunction "-_-") (pintype "passive"))
      (node (ref "U$5") (pin "P$1") (pinfunction "GND_P$1") (pintype "power_in"))
      (node (ref "U$5") (pin "P$10") (pinfunction "RTS_P$10") (pintype "input"))
      (node (ref "U$5") (pin "P$14") (pinfunction "GND_P$14") (pintype "power_in"))
      (node (ref "U$5") (pin "P$15") (pinfunction "GND_P$15") (pintype "power_in"))
      (node (ref "U$5") (pin "P$17") (pinfunction "GND_P$17") (pintype "power_in"))
      (node (ref "U$5") (pin "P$19") (pinfunction "GND_P$19") (pintype "power_in"))
      (node (ref "U$5") (pin "P$2") (pinfunction "GND_P$2") (pintype "power_in"))
      (node (ref "U$5") (pin "P$20") (pinfunction "GND_P$20") (pintype "power_in"))
      (node (ref "U$5") (pin "P$21") (pinfunction "GND_P$21") (pintype "power_in"))
      (node (ref "U$5") (pin "P$22") (pinfunction "GND_P$22") (pintype "power_in"))
      (node (ref "U$5") (pin "P$23") (pinfunction "GND_P$23") (pintype "power_in"))
      (node (ref "U$5") (pin "P$25") (pinfunction "GND_P$25") (pintype "power_in"))
      (node (ref "U$5") (pin "P$28") (pinfunction "GND_P$28") (pintype "power_in"))
      (node (ref "U$5") (pin "P$29") (pinfunction "GND_P$29") (pintype "power_in"))
      (node (ref "U$5") (pin "P$3") (pinfunction "GND_P$3") (pintype "power_in"))
      (node (ref "U$5") (pin "P$30") (pinfunction "GND_P$30") (pintype "power_in"))
      (node (ref "U$5") (pin "P$31") (pinfunction "GND_P$31") (pintype "power_in"))
      (node (ref "U$5") (pin "P$32") (pinfunction "GND_P$32") (pintype "power_in"))
      (node (ref "U$5") (pin "P$33") (pinfunction "GND_P$33") (pintype "power_in"))
      (node (ref "U$5") (pin "P$34") (pinfunction "GND_P$34") (pintype "power_in"))
      (node (ref "U$5") (pin "P$35") (pinfunction "GND_P$35") (pintype "power_in"))
      (node (ref "U$5") (pin "P$36") (pinfunction "GND_P$36") (pintype "power_in"))
      (node (ref "U$5") (pin "P$37") (pinfunction "GND_P$37") (pintype "power_in"))
      (node (ref "U$5") (pin "P$42") (pinfunction "GND_P$42") (pintype "power_in"))
      (node (ref "U$5") (pin "P$43") (pinfunction "GND_P$43") (pintype "power_in"))
      (node (ref "U$5") (pin "P$44") (pinfunction "GND_P$44") (pintype "power_in"))
      (node (ref "U$5") (pin "P$45") (pinfunction "GND_P$45") (pintype "power_in"))
      (node (ref "U$5") (pin "P$46") (pinfunction "GND_P$46") (pintype "power_in"))
      (node (ref "U$5") (pin "P$47") (pinfunction "GND_P$47") (pintype "power_in"))
      (node (ref "U$5") (pin "P$48") (pinfunction "GND_P$48") (pintype "power_in"))
      (node (ref "U$5") (pin "P$49") (pinfunction "GND_P$49") (pintype "power_in"))
      (node (ref "U$5") (pin "P$5") (pinfunction "GND_P$5") (pintype "power_in"))
      (node (ref "U$5") (pin "P$50") (pinfunction "GND_P$50") (pintype "power_in"))
      (node (ref "U$5") (pin "P$54") (pinfunction "GND_P$54") (pintype "power_in"))
      (node (ref "U$5") (pin "P$55") (pinfunction "GND_P$55") (pintype "power_in"))
      (node (ref "U$5") (pin "P$57") (pinfunction "GND_P$57") (pintype "power_in"))
      (node (ref "U$5") (pin "P$58") (pinfunction "GND_P$58") (pintype "power_in"))
      (node (ref "U$5") (pin "P$59") (pinfunction "GND_P$59") (pintype "power_in"))
      (node (ref "U$5") (pin "P$6") (pinfunction "GND_P$6") (pintype "power_in"))
      (node (ref "U$5") (pin "P$60") (pinfunction "GND_P$60") (pintype "power_in"))
      (node (ref "U$5") (pin "P$61") (pinfunction "GND_P$61") (pintype "power_in"))
      (node (ref "U$5") (pin "P$63") (pinfunction "GND_P$63") (pintype "power_in"))
      (node (ref "U$5") (pin "P$64") (pinfunction "GND_P$64") (pintype "power_in"))
      (node (ref "U$5") (pin "P$65") (pinfunction "GND_P$65") (pintype "power_in"))
      (node (ref "U$5") (pin "P$66") (pinfunction "GND_P$66") (pintype "power_in"))
      (node (ref "U$5") (pin "P$67") (pinfunction "GND_P$67") (pintype "power_in"))
      (node (ref "U$5") (pin "P$68") (pinfunction "GND_P$68") (pintype "power_in"))
      (node (ref "U$5") (pin "P$69") (pinfunction "GND_P$69") (pintype "power_in"))
      (node (ref "U$5") (pin "P$7") (pinfunction "GND_P$7") (pintype "power_in"))
      (node (ref "U$5") (pin "P$70") (pinfunction "GND_P$70") (pintype "power_in"))
      (node (ref "U$5") (pin "P$71") (pinfunction "GND_P$71") (pintype "power_in"))
      (node (ref "U$5") (pin "P$72") (pinfunction "GND_P$72") (pintype "power_in"))
      (node (ref "U$5") (pin "P$73") (pinfunction "GND_P$73") (pintype "power_in"))
      (node (ref "U$5") (pin "P$74") (pinfunction "GND_P$74") (pintype "power_in"))
      (node (ref "U$5") (pin "P$75") (pinfunction "GND_P$75") (pintype "power_in"))
      (node (ref "U$5") (pin "P$76") (pinfunction "GND_P$76") (pintype "power_in"))
      (node (ref "U$5") (pin "P$77") (pinfunction "GND_P$77") (pintype "power_in"))
      (node (ref "U$5") (pin "P$78") (pinfunction "GND_P$78") (pintype "power_in"))
      (node (ref "U$5") (pin "P$79") (pinfunction "GND_P$79") (pintype "power_in"))
      (node (ref "U$5") (pin "P$80") (pinfunction "GND_P$80") (pintype "power_in"))
      (node (ref "U$5") (pin "P$81") (pinfunction "GND_P$81") (pintype "power_in"))
      (node (ref "U$5") (pin "P$82") (pinfunction "GND_P$82") (pintype "power_in"))
      (node (ref "U$5") (pin "P$83") (pinfunction "GND_P$83") (pintype "power_in"))
      (node (ref "U$5") (pin "P$84") (pinfunction "GND_P$84") (pintype "power_in"))
      (node (ref "U$5") (pin "P$85") (pinfunction "GND_P$85") (pintype "power_in"))
      (node (ref "U$5") (pin "P$86") (pinfunction "GND_P$86") (pintype "power_in"))
      (node (ref "U$5") (pin "P$87") (pinfunction "GND_P$87") (pintype "power_in"))
      (node (ref "U$5") (pin "P$88") (pinfunction "GND_P$88") (pintype "power_in"))
      (node (ref "U$5") (pin "P$89") (pinfunction "GND_P$89") (pintype "power_in"))
      (node (ref "U$5") (pin "P$9") (pinfunction "GND_P$9") (pintype "power_in"))
      (node (ref "U$5") (pin "P$90") (pinfunction "GND_P$90") (pintype "power_in"))
      (node (ref "U$5") (pin "P$91") (pinfunction "GND_P$91") (pintype "power_in"))
      (node (ref "U$5") (pin "P$92") (pinfunction "GND_P$92") (pintype "power_in"))
      (node (ref "U$5") (pin "P$93") (pinfunction "GND_P$93") (pintype "power_in"))
      (node (ref "U$5") (pin "P$94") (pinfunction "GND_P$94") (pintype "power_in"))
      (node (ref "U$5") (pin "P$95") (pinfunction "GND_P$95") (pintype "power_in"))
      (node (ref "U$5") (pin "P$96") (pinfunction "GND_P$96") (pintype "power_in"))
      (node (ref "U1") (pin "P$9") (pinfunction "GND_P$9") (pintype "bidirectional"))
      (node (ref "X4") (pin "1") (pinfunction "GND_1") (pintype "passive"))
      (node (ref "X4") (pin "2") (pinfunction "GND_2") (pintype "passive"))
    )
    (net (code "26") (name "AVDDOUT") (class "Default")
      (node (ref "ADE9000") (pin "25") (pinfunction "AVDDOUT_25") (pintype "bidirectional"))
      (node (ref "C6") (pin "1") (pinfunction "1_1") (pintype "passive"))
      (node (ref "C7") (pin "1") (pinfunction "1_1") (pintype "passive"))
    )
    (net (code "27") (name "B-485-1-RX-TIME") (class "Default")
      (node (ref "JP1") (pin "6") (pinfunction "6_6") (pintype "passive"))
      (node (ref "JP6") (pin "2") (pinfunction "2_2") (pintype "passive"))
    )
    (net (code "28") (name "CF1_ADE") (class "Default")
      (node (ref "ADE9000") (pin "33") (pinfunction "CF1_33") (pintype "bidirectional"))
      (node (ref "ADUM4151") (pin "12") (pinfunction "VIC_12") (pintype "bidirectional"))
    )
    (net (code "29") (name "CLKIN") (class "Default")
      (node (ref "ADE9000") (pin "29") (pinfunction "CLKIN_29") (pintype "bidirectional"))
      (node (ref "C9") (pin "1") (pinfunction "1_1") (pintype "passive"))
      (node (ref "Q1") (pin "3") (pinfunction "2_3") (pintype "passive"))
    )
    (net (code "30") (name "CLKOUT") (class "Default")
      (node (ref "ADE9000") (pin "30") (pinfunction "CLKOUT_30") (pintype "bidirectional"))
      (node (ref "C8") (pin "1") (pinfunction "1_1") (pintype "passive"))
      (node (ref "Q1") (pin "1") (pinfunction "1_1") (pintype "passive"))
    )
    (net (code "31") (name "CRS") (class "Default")
      (node (ref "SV2") (pin "10") (pinfunction "10_10") (pintype "passive"))
      (node (ref "U4") (pin "12") (pinfunction "IO27_12") (pintype "bidirectional"))
    )
    (net (code "32") (name "DAC1") (class "Default")
      (node (ref "JP4") (pin "10") (pinfunction "10_10") (pintype "passive"))
      (node (ref "X7") (pin "4") (pinfunction "1_4") (pintype "passive"))
    )
    (net (code "33") (name "DIO0_LORA") (class "Default")
      (node (ref "JP3") (pin "8") (pinfunction "8_8") (pintype "passive"))
    )
    (net (code "34") (name "DIO1_LORA") (class "Default")
      (node (ref "JP3") (pin "3") (pinfunction "3_3") (pintype "passive"))
    )
    (net (code "35") (name "DVDDOUT") (class "Default")
      (node (ref "ADE9000") (pin "3") (pinfunction "DVDDOUT_3") (pintype "bidirectional"))
      (node (ref "C2") (pin "1") (pinfunction "1_1") (pintype "passive"))
      (node (ref "C3") (pin "1") (pinfunction "1_1") (pintype "passive"))
    )
    (net (code "36") (name "ESP_RESET") (class "Default")
      (node (ref "C40U2") (pin "2") (pinfunction "2_2") (pintype "passive"))
      (node (ref "D1") (pin "C") (pinfunction "C_C") (pintype "passive"))
      (node (ref "R15E4") (pin "2") (pinfunction "2_2") (pintype "passive"))
      (node (ref "U4") (pin "3") (pinfunction "EN_3") (pintype "input"))
      (node (ref "X5") (pin "2") (pinfunction "S_2") (pintype "passive"))
    )
    (net (code "37") (name "GND-485-1") (class "Default")
      (node (ref "JP1") (pin "8") (pinfunction "8_8") (pintype "passive"))
      (node (ref "JP6") (pin "1") (pinfunction "1_1") (pintype "passive"))
    )
    (net (code "38") (name "GND-ADE900") (class "Default")
      (node (ref "ADE9000") (pin "13") (pinfunction "INP_13") (pintype "bidirectional"))
      (node (ref "ADE9000") (pin "14") (pinfunction "INN_14") (pintype "bidirectional"))
      (node (ref "ADE9000") (pin "15") (pinfunction "REFGND_15") (pintype "bidirectional"))
      (node (ref "ADE9000") (pin "17") (pinfunction "NC1_17") (pintype "bidirectional"))
      (node (ref "ADE9000") (pin "18") (pinfunction "NC2_18") (pintype "bidirectional"))
      (node (ref "ADE9000") (pin "2") (pinfunction "DGND_2") (pintype "bidirectional"))
      (node (ref "ADE9000") (pin "26") (pinfunction "AGND_26") (pintype "bidirectional"))
      (node (ref "ADE9000") (pin "28") (pinfunction "GND_28") (pintype "bidirectional"))
      (node (ref "ADE9000") (pin "GND") (pinfunction "PADGND_GND") (pintype "bidirectional"))
      (node (ref "ADUM4151") (pin "11") (pinfunction "GND22_11") (pintype "bidirectional"))
      (node (ref "ADUM4151") (pin "19") (pinfunction "GND2_19") (pintype "bidirectional"))
      (node (ref "ADUM6402-2") (pin "10") (pinfunction "VSEL_10") (pintype "bidirectional"))
      (node (ref "ADUM6402-2") (pin "15") (pinfunction "GNDISO_15") (pintype "bidirectional"))
      (node (ref "ADUM6402-2") (pin "9") (pinfunction "GND_ISO_1_9") (pintype "bidirectional"))
      (node (ref "C1") (pin "2") (pinfunction "2_2") (pintype "passive"))
      (node (ref "C10") (pin "2") (pinfunction "2_2") (pintype "passive"))
      (node (ref "C100") (pin "1") (pinfunction "1_1") (pintype "passive"))
      (node (ref "C11") (pin "2") (pinfunction "2_2") (pintype "passive"))
      (node (ref "C12") (pin "1") (pinfunction "1_1") (pintype "passive"))
      (node (ref "C13") (pin "1") (pinfunction "1_1") (pintype "passive"))
      (node (ref "C15") (pin "1") (pinfunction "1_1") (pintype "passive"))
      (node (ref "C16") (pin "1") (pinfunction "1_1") (pintype "passive"))
      (node (ref "C18") (pin "1") (pinfunction "1_1") (pintype "passive"))
      (node (ref "C19") (pin "2") (pinfunction "2_2") (pintype "passive"))
      (node (ref "C2") (pin "2") (pinfunction "2_2") (pintype "passive"))
      (node (ref "C20") (pin "1") (pinfunction "1_1") (pintype "passive"))
      (node (ref "C200") (pin "1") (pinfunction "1_1") (pintype "passive"))
      (node (ref "C21") (pin "2") (pinfunction "2_2") (pintype "passive"))
      (node (ref "C22") (pin "1") (pinfunction "1_1") (pintype "passive"))
      (node (ref "C23") (pin "2") (pinfunction "2_2") (pintype "passive"))
      (node (ref "C3") (pin "2") (pinfunction "2_2") (pintype "passive"))
      (node (ref "C32A") (pin "2") (pinfunction "2_2") (pintype "passive"))
      (node (ref "C33A") (pin "2") (pinfunction "2_2") (pintype "passive"))
      (node (ref "C34A") (pin "2") (pinfunction "2_2") (pintype "passive"))
      (node (ref "C35A") (pin "2") (pinfunction "2_2") (pintype "passive"))
      (node (ref "C4") (pin "2") (pinfunction "2_2") (pintype "passive"))
      (node (ref "C5") (pin "2") (pinfunction "2_2") (pintype "passive"))
      (node (ref "C6") (pin "2") (pinfunction "2_2") (pintype "passive"))
      (node (ref "C7") (pin "2") (pinfunction "2_2") (pintype "passive"))
      (node (ref "C8") (pin "2") (pinfunction "2_2") (pintype "passive"))
      (node (ref "C9") (pin "2") (pinfunction "2_2") (pintype "passive"))
      (node (ref "HKLP1") (pin "P$2") (pinfunction "AC2_P$2") (pintype "bidirectional"))
      (node (ref "Q2") (pin "3") (pinfunction "3_3") (pintype "passive"))
      (node (ref "Q3") (pin "3") (pinfunction "3_3") (pintype "passive"))
      (node (ref "Q4") (pin "3") (pinfunction "3_3") (pintype "passive"))
      (node (ref "Q5") (pin "3") (pinfunction "3_3") (pintype "passive"))
      (node (ref "Q6") (pin "3") (pinfunction "3_3") (pintype "passive"))
      (node (ref "Q7") (pin "3") (pinfunction "3_3") (pintype "passive"))
      (node (ref "R10") (pin "2") (pinfunction "2_2") (pintype "passive"))
      (node (ref "R104") (pin "2") (pinfunction "2_2") (pintype "passive"))
      (node (ref "R11") (pin "2") (pinfunction "2_2") (pintype "passive"))
      (node (ref "R2") (pin "2") (pinfunction "2_2") (pintype "passive"))
      (node (ref "R20") (pin "2") (pinfunction "2_2") (pintype "passive"))
      (node (ref "R200") (pin "2") (pinfunction "2_2") (pintype "passive"))
      (node (ref "R34") (pin "2") (pinfunction "2_2") (pintype "passive"))
      (node (ref "R48") (pin "2") (pinfunction "2_2") (pintype "passive"))
      (node (ref "R5") (pin "2") (pinfunction "2_2") (pintype "passive"))
      (node (ref "SP1") (pin "1") (pinfunction "1_1") (pintype "passive"))
      (node (ref "SP2") (pin "1") (pinfunction "1_1") (pintype "passive"))
      (node (ref "SP3") (pin "1") (pinfunction "1_1") (pintype "passive"))
      (node (ref "SP@") (pin "2") (pinfunction "2_2") (pintype "passive"))
      (node (ref "SP@1") (pin "2") (pinfunction "2_2") (pintype "passive"))
      (node (ref "SP@2") (pin "2") (pinfunction "2_2") (pintype "passive"))
      (node (ref "X2") (pin "1") (pinfunction "KL_1") (pintype "passive"))
    )
    (net (code "39") (name "GND-IN12") (class "Default")
      (node (ref "JP4") (pin "7") (pinfunction "7_7") (pintype "passive"))
      (node (ref "X7") (pin "8") (pinfunction "1_8") (pintype "passive"))
    )
    (net (code "40") (name "GND-IO1{slash}4") (class "Default")
      (node (ref "JP4") (pin "1") (pinfunction "1_1") (pintype "passive"))
      (node (ref "X8") (pin "1") (pinfunction "KL_1") (pintype "passive"))
    )
    (net (code "41") (name "GPIO1") (class "Default")
      (node (ref "R19") (pin "2") (pinfunction "2_2") (pintype "passive"))
      (node (ref "U$5") (pin "P$16") (pinfunction "GPIO1_P$16") (pintype "bidirectional"))
    )
    (net (code "42") (name "IAN") (class "Default")
      (node (ref "ADE9000") (pin "8") (pinfunction "IAN_8") (pintype "bidirectional"))
      (node (ref "C19") (pin "1") (pinfunction "1_1") (pintype "passive"))
      (node (ref "R36") (pin "2") (pinfunction "2_2") (pintype "passive"))
    )
    (net (code "43") (name "IAP") (class "Default")
      (node (ref "ADE9000") (pin "7") (pinfunction "IAP_7") (pintype "bidirectional"))
      (node (ref "C18") (pin "2") (pinfunction "2_2") (pintype "passive"))
      (node (ref "R35") (pin "2") (pinfunction "2_2") (pintype "passive"))
    )
    (net (code "44") (name "IBN") (class "Default")
      (node (ref "ADE9000") (pin "10") (pinfunction "IBN_10") (pintype "bidirectional"))
      (node (ref "C21") (pin "1") (pinfunction "1_1") (pintype "passive"))
      (node (ref "R31") (pin "2") (pinfunction "2_2") (pintype "passive"))
    )
    (net (code "45") (name "IBP") (class "Default")
      (node (ref "ADE9000") (pin "9") (pinfunction "IBP_9") (pintype "bidirectional"))
      (node (ref "C20") (pin "2") (pinfunction "2_2") (pintype "passive"))
      (node (ref "R30") (pin "2") (pinfunction "2_2") (pintype "passive"))
    )
    (net (code "46") (name "ICN") (class "Default")
      (node (ref "ADE9000") (pin "12") (pinfunction "ICN_12") (pintype "bidirectional"))
      (node (ref "C23") (pin "1") (pinfunction "1_1") (pintype "passive"))
      (node (ref "R45") (pin "2") (pinfunction "2_2") (pintype "passive"))
    )
    (net (code "47") (name "ICP") (class "Default")
      (node (ref "ADE9000") (pin "11") (pinfunction "ICP_11") (pintype "bidirectional"))
      (node (ref "C22") (pin "2") (pinfunction "2_2") (pintype "passive"))
      (node (ref "R44") (pin "2") (pinfunction "2_2") (pintype "passive"))
    )
    (net (code "48") (name "IL1+") (class "Default")
      (node (ref "0.05/2W1") (pin "1") (pinfunction "1_1") (pintype "passive"))
      (node (ref "R23") (pin "1") (pinfunction "1_1") (pintype "passive"))
      (node (ref "X3") (pin "2") (pinfunction "KL_2") (pintype "passive"))
    )
    (net (code "49") (name "IL1-") (class "Default")
      (node (ref "0.05/2W1") (pin "2") (pinfunction "2_2") (pintype "passive"))
      (node (ref "R24") (pin "1") (pinfunction "1_1") (pintype "passive"))
      (node (ref "X3") (pin "1") (pinfunction "KL_1") (pintype "passive"))
    )
    (net (code "50") (name "IL2+") (class "Default")
      (node (ref "0.05/2W2") (pin "1") (pinfunction "1_1") (pintype "passive"))
      (node (ref "R37") (pin "1") (pinfunction "1_1") (pintype "passive"))
      (node (ref "X3") (pin "4") (pinfunction "KL_4") (pintype "passive"))
    )
    (net (code "51") (name "IL2-") (class "Default")
      (node (ref "0.05/2W2") (pin "2") (pinfunction "2_2") (pintype "passive"))
      (node (ref "R38") (pin "1") (pinfunction "1_1") (pintype "passive"))
      (node (ref "X3") (pin "3") (pinfunction "KL_3") (pintype "passive"))
    )
    (net (code "52") (name "IL3+") (class "Default")
      (node (ref "0.05/2W") (pin "1") (pinfunction "1_1") (pintype "passive"))
      (node (ref "R49") (pin "1") (pinfunction "1_1") (pintype "passive"))
      (node (ref "X3") (pin "6") (pinfunction "KL_6") (pintype "passive"))
    )
    (net (code "53") (name "IL3-") (class "Default")
      (node (ref "0.05/2W") (pin "2") (pinfunction "2_2") (pintype "passive"))
      (node (ref "R50") (pin "1") (pinfunction "1_1") (pintype "passive"))
      (node (ref "X3") (pin "5") (pinfunction "KL_5") (pintype "passive"))
    )
    (net (code "54") (name "IN1") (class "Default")
      (node (ref "JP4") (pin "8") (pinfunction "8_8") (pintype "passive"))
      (node (ref "X7") (pin "7") (pinfunction "1_7") (pintype "passive"))
    )
    (net (code "55") (name "IN2") (class "Default")
      (node (ref "JP4") (pin "9") (pinfunction "9_9") (pintype "passive"))
      (node (ref "X7") (pin "6") (pinfunction "1_6") (pintype "passive"))
    )
    (net (code "56") (name "INT-DISPLAY") (class "Default")
      (node (ref "JP1") (pin "5") (pinfunction "5_5") (pintype "passive"))
      (node (ref "R15E7") (pin "2") (pinfunction "2_2") (pintype "passive"))
      (node (ref "X1") (pin "1") (pinfunction "S_1") (pintype "passive"))
    )
    (net (code "57") (name "INT-MCP23017") (class "Default")
      (node (ref "JP1") (pin "7") (pinfunction "7_7") (pintype "passive"))
      (node (ref "U4") (pin "29") (pinfunction "IO5_29") (pintype "bidirectional"))
    )
    (net (code "58") (name "INT-RTC") (class "Default")
      (node (ref "JP1") (pin "2") (pinfunction "2_2") (pintype "passive"))
      (node (ref "SV1") (pin "3") (pinfunction "3_3") (pintype "passive"))
    )
    (net (code "59") (name "INT-TIME") (class "Default")
      (node (ref "JP2") (pin "3") (pinfunction "3_3") (pintype "passive"))
      (node (ref "R18") (pin "1") (pinfunction "1_1") (pintype "passive"))
      (node (ref "U$1") (pin "!INT/!!SQW") (pinfunction "~{INT/~SQW}_!INT/!!SQW") (pintype "bidirectional"))
    )
    (net (code "60") (name "IRQ1_ADE") (class "Default")
      (node (ref "ADE9000") (pin "32") (pinfunction "IRQ1_32") (pintype "bidirectional"))
      (node (ref "ADUM6402-2") (pin "11") (pinfunction "VID_11") (pintype "bidirectional"))
    )
    (net (code "61") (name "MDC") (class "Default")
      (node (ref "SV2") (pin "12") (pinfunction "12_12") (pintype "passive"))
      (node (ref "U4") (pin "37") (pinfunction "IO23_37") (pintype "bidirectional"))
    )
    (net (code "62") (name "MDIO") (class "Default")
      (node (ref "SV2") (pin "11") (pinfunction "11_11") (pintype "passive"))
      (node (ref "U4") (pin "30") (pinfunction "IO18_30") (pintype "bidirectional"))
    )
    (net (code "63") (name "MISO-TRI") (class "Default")
      (node (ref "U$4") (pin "4") (pinfunction "Y_4") (pintype "bidirectional"))
      (node (ref "U4") (pin "14") (pinfunction "IO12_14") (pintype "bidirectional"))
    )
    (net (code "64") (name "MISO_ADE") (class "Default")
      (node (ref "ADE9000") (pin "38") (pinfunction "MISO_38") (pintype "bidirectional"))
      (node (ref "ADUM4151") (pin "16") (pinfunction "SO_16") (pintype "bidirectional"))
    )
    (net (code "65") (name "MISO_LORA") (class "Default")
      (node (ref "JP3") (pin "6") (pinfunction "6_6") (pintype "passive"))
    )
    (net (code "66") (name "MOSI_ADE") (class "Default")
      (node (ref "ADE9000") (pin "39") (pinfunction "MOSI_39") (pintype "bidirectional"))
      (node (ref "ADUM4151") (pin "17") (pinfunction "SI_17") (pintype "bidirectional"))
    )
    (net (code "67") (name "MOSI_LORA") (class "Default")
      (node (ref "JP3") (pin "12") (pinfunction "12_12") (pintype "passive"))
    )
    (net (code "68") (name "NINT{slash}REFCLK") (class "Default")
      (node (ref "SJ3") (pin "1") (pinfunction "1_1") (pintype "passive"))
      (node (ref "SJ5") (pin "2") (pinfunction "2_2") (pintype "passive"))
    )
    (net (code "69") (name "NINT{slash}REFCLK1") (class "Default")
      (node (ref "R15E11") (pin "2") (pinfunction "2_2") (pintype "passive"))
      (node (ref "SJ5") (pin "1") (pinfunction "1_1") (pintype "passive"))
      (node (ref "SV2") (pin "9") (pinfunction "9_9") (pintype "passive"))
    )
    (net (code "70") (name "Net-(D5-PadC)") (class "Default")
      (node (ref "D5") (pin "C") (pinfunction "C_C") (pintype "passive"))
      (node (ref "R32") (pin "2") (pinfunction "2_2") (pintype "passive"))
    )
    (net (code "71") (name "Net-(FUSE2-Pad1)") (class "Default")
      (node (ref "FUSE2") (pin "1") (pinfunction "1_1") (pintype "passive"))
      (node (ref "L1") (pin "1") (pinfunction "1_1") (pintype "passive"))
    )
    (net (code "72") (name "Net-(FUSE3-Pad1)") (class "Default")
      (node (ref "FUSE3") (pin "1") (pinfunction "1_1") (pintype "passive"))
      (node (ref "L3") (pin "1") (pinfunction "1_1") (pintype "passive"))
    )
    (net (code "73") (name "Net-(HKLP1-+VO)") (class "Default")
      (node (ref "HKLP1") (pin "P$4") (pinfunction "+VO_P$4") (pintype "bidirectional"))
      (node (ref "SJ1") (pin "2") (pinfunction "2_2") (pintype "passive"))
    )
    (net (code "74") (name "Net-(HKLP1-AC1)") (class "Default")
      (node (ref "HKLP1") (pin "P$1") (pinfunction "AC1_P$1") (pintype "bidirectional"))
      (node (ref "SJ2") (pin "2") (pinfunction "2_2") (pintype "passive"))
    )
    (net (code "75") (name "Net-(L1-Pad2)") (class "Default")
      (node (ref "L1") (pin "2") (pinfunction "2_2") (pintype "passive"))
      (node (ref "R101") (pin "2") (pinfunction "2_2") (pintype "passive"))
    )
    (net (code "76") (name "Net-(L2-Pad2)") (class "Default")
      (node (ref "L2") (pin "2") (pinfunction "2_2") (pintype "passive"))
      (node (ref "R6") (pin "2") (pinfunction "2_2") (pintype "passive"))
    )
    (net (code "77") (name "Net-(L3-Pad2)") (class "Default")
      (node (ref "L3") (pin "2") (pinfunction "2_2") (pintype "passive"))
      (node (ref "R12") (pin "2") (pinfunction "2_2") (pintype "passive"))
    )
    (net (code "78") (name "Net-(PTC1-Pad1)") (class "Default")
      (node (ref "PTC1") (pin "1") (pinfunction "1_1") (pintype "passive"))
      (node (ref "X7") (pin "1") (pinfunction "1_1") (pintype "passive"))
    )
    (net (code "79") (name "Net-(Q2-Pad1)") (class "Default")
      (node (ref "Q2") (pin "1") (pinfunction "1_1") (pintype "passive"))
      (node (ref "Q3") (pin "2") (pinfunction "2_2") (pintype "passive"))
      (node (ref "R16") (pin "1") (pinfunction "1_1") (pintype "passive"))
      (node (ref "R21") (pin "1") (pinfunction "1_1") (pintype "passive"))
      (node (ref "R23") (pin "2") (pinfunction "2_2") (pintype "passive"))
    )
    (net (code "80") (name "Net-(Q2-Pad2)") (class "Default")
      (node (ref "Q2") (pin "2") (pinfunction "2_2") (pintype "passive"))
      (node (ref "Q3") (pin "1") (pinfunction "1_1") (pintype "passive"))
      (node (ref "R22") (pin "2") (pinfunction "2_2") (pintype "passive"))
      (node (ref "R25") (pin "2") (pinfunction "2_2") (pintype "passive"))
    )
    (net (code "81") (name "Net-(Q4-Pad1)") (class "Default")
      (node (ref "Q4") (pin "1") (pinfunction "1_1") (pintype "passive"))
      (node (ref "Q5") (pin "2") (pinfunction "2_2") (pintype "passive"))
      (node (ref "R26") (pin "1") (pinfunction "1_1") (pintype "passive"))
      (node (ref "R28") (pin "1") (pinfunction "1_1") (pintype "passive"))
      (node (ref "R37") (pin "2") (pinfunction "2_2") (pintype "passive"))
    )
    (net (code "82") (name "Net-(Q4-Pad2)") (class "Default")
      (node (ref "Q4") (pin "2") (pinfunction "2_2") (pintype "passive"))
      (node (ref "Q5") (pin "1") (pinfunction "1_1") (pintype "passive"))
      (node (ref "R29") (pin "2") (pinfunction "2_2") (pintype "passive"))
      (node (ref "R39") (pin "2") (pinfunction "2_2") (pintype "passive"))
    )
    (net (code "83") (name "Net-(Q6-Pad1)") (class "Default")
      (node (ref "Q6") (pin "1") (pinfunction "1_1") (pintype "passive"))
      (node (ref "Q7") (pin "2") (pinfunction "2_2") (pintype "passive"))
      (node (ref "R40") (pin "1") (pinfunction "1_1") (pintype "passive"))
      (node (ref "R42") (pin "1") (pinfunction "1_1") (pintype "passive"))
      (node (ref "R49") (pin "2") (pinfunction "2_2") (pintype "passive"))
    )
    (net (code "84") (name "Net-(Q6-Pad2)") (class "Default")
      (node (ref "Q6") (pin "2") (pinfunction "2_2") (pintype "passive"))
      (node (ref "Q7") (pin "1") (pinfunction "1_1") (pintype "passive"))
      (node (ref "R43") (pin "2") (pinfunction "2_2") (pintype "passive"))
      (node (ref "R51") (pin "2") (pinfunction "2_2") (pintype "passive"))
    )
    (net (code "85") (name "Net-(Q8-B)") (class "Default")
      (node (ref "Q8") (pin "1") (pinfunction "B_1") (pintype "passive"))
      (node (ref "R19") (pin "1") (pinfunction "1_1") (pintype "passive"))
    )
    (net (code "86") (name "Net-(Q8-C)") (class "Default")
      (node (ref "Q8") (pin "3") (pinfunction "C_3") (pintype "passive"))
      (node (ref "R32") (pin "1") (pinfunction "1_1") (pintype "passive"))
    )
    (net (code "87") (name "Net-(R1-Pad1)") (class "Default")
      (node (ref "R1") (pin "1") (pinfunction "1_1") (pintype "passive"))
      (node (ref "R4") (pin "1") (pinfunction "1_1") (pintype "passive"))
    )
    (net (code "88") (name "Net-(R1-Pad2)") (class "Default")
      (node (ref "R1") (pin "2") (pinfunction "2_2") (pintype "passive"))
      (node (ref "R101") (pin "1") (pinfunction "1_1") (pintype "passive"))
    )
    (net (code "89") (name "Net-(R6-Pad1)") (class "Default")
      (node (ref "R6") (pin "1") (pinfunction "1_1") (pintype "passive"))
      (node (ref "R8") (pin "2") (pinfunction "2_2") (pintype "passive"))
    )
    (net (code "90") (name "Net-(R7-Pad2)") (class "Default")
      (node (ref "R7") (pin "2") (pinfunction "2_2") (pintype "passive"))
      (node (ref "R9") (pin "2") (pinfunction "2_2") (pintype "passive"))
    )
    (net (code "91") (name "Net-(R8-Pad1)") (class "Default")
      (node (ref "R8") (pin "1") (pinfunction "1_1") (pintype "passive"))
      (node (ref "R9") (pin "1") (pinfunction "1_1") (pintype "passive"))
    )
    (net (code "92") (name "Net-(R12-Pad1)") (class "Default")
      (node (ref "R12") (pin "1") (pinfunction "1_1") (pintype "passive"))
      (node (ref "R14") (pin "2") (pinfunction "2_2") (pintype "passive"))
    )
    (net (code "93") (name "Net-(R13-Pad2)") (class "Default")
      (node (ref "R13") (pin "2") (pinfunction "2_2") (pintype "passive"))
      (node (ref "R15") (pin "2") (pinfunction "2_2") (pintype "passive"))
    )
    (net (code "94") (name "Net-(R14-Pad1)") (class "Default")
      (node (ref "R14") (pin "1") (pinfunction "1_1") (pintype "passive"))
      (node (ref "R15") (pin "1") (pinfunction "1_1") (pintype "passive"))
    )
    (net (code "95") (name "Net-(R16-Pad2)") (class "Default")
      (node (ref "R16") (pin "2") (pinfunction "2_2") (pintype "passive"))
      (node (ref "R17") (pin "1") (pinfunction "1_1") (pintype "passive"))
      (node (ref "R20") (pin "1") (pinfunction "1_1") (pintype "passive"))
    )
    (net (code "96") (name "Net-(R17-Pad2)") (class "Default")
      (node (ref "R17") (pin "2") (pinfunction "2_2") (pintype "passive"))
      (node (ref "R24") (pin "2") (pinfunction "2_2") (pintype "passive"))
      (node (ref "R25") (pin "1") (pinfunction "1_1") (pintype "passive"))
    )
    (net (code "97") (name "Net-(R21-Pad2)") (class "Default")
      (node (ref "R21") (pin "2") (pinfunction "2_2") (pintype "passive"))
      (node (ref "R35") (pin "1") (pinfunction "1_1") (pintype "passive"))
      (node (ref "SP1") (pin "2") (pinfunction "2_2") (pintype "passive"))
    )
    (net (code "98") (name "Net-(R22-Pad1)") (class "Default")
      (node (ref "R22") (pin "1") (pinfunction "1_1") (pintype "passive"))
      (node (ref "R36") (pin "1") (pinfunction "1_1") (pintype "passive"))
      (node (ref "SP@") (pin "1") (pinfunction "1_1") (pintype "passive"))
    )
    (net (code "99") (name "Net-(R26-Pad2)") (class "Default")
      (node (ref "R26") (pin "2") (pinfunction "2_2") (pintype "passive"))
      (node (ref "R27") (pin "1") (pinfunction "1_1") (pintype "passive"))
      (node (ref "R34") (pin "1") (pinfunction "1_1") (pintype "passive"))
    )
    (net (code "100") (name "Net-(R27-Pad2)") (class "Default")
      (node (ref "R27") (pin "2") (pinfunction "2_2") (pintype "passive"))
      (node (ref "R38") (pin "2") (pinfunction "2_2") (pintype "passive"))
      (node (ref "R39") (pin "1") (pinfunction "1_1") (pintype "passive"))
    )
    (net (code "101") (name "Net-(R28-Pad2)") (class "Default")
      (node (ref "R28") (pin "2") (pinfunction "2_2") (pintype "passive"))
      (node (ref "R30") (pin "1") (pinfunction "1_1") (pintype "passive"))
      (node (ref "SP2") (pin "2") (pinfunction "2_2") (pintype "passive"))
    )
    (net (code "102") (name "Net-(R29-Pad1)") (class "Default")
      (node (ref "R29") (pin "1") (pinfunction "1_1") (pintype "passive"))
      (node (ref "R31") (pin "1") (pinfunction "1_1") (pintype "passive"))
      (node (ref "SP@1") (pin "1") (pinfunction "1_1") (pintype "passive"))
    )
    (net (code "103") (name "Net-(R40-Pad2)") (class "Default")
      (node (ref "R40") (pin "2") (pinfunction "2_2") (pintype "passive"))
      (node (ref "R41") (pin "1") (pinfunction "1_1") (pintype "passive"))
      (node (ref "R48") (pin "1") (pinfunction "1_1") (pintype "passive"))
    )
    (net (code "104") (name "Net-(R41-Pad2)") (class "Default")
      (node (ref "R41") (pin "2") (pinfunction "2_2") (pintype "passive"))
      (node (ref "R50") (pin "2") (pinfunction "2_2") (pintype "passive"))
      (node (ref "R51") (pin "1") (pinfunction "1_1") (pintype "passive"))
    )
    (net (code "105") (name "Net-(R42-Pad2)") (class "Default")
      (node (ref "R42") (pin "2") (pinfunction "2_2") (pintype "passive"))
      (node (ref "R44") (pin "1") (pinfunction "1_1") (pintype "passive"))
      (node (ref "SP3") (pin "2") (pinfunction "2_2") (pintype "passive"))
    )
    (net (code "106") (name "Net-(R43-Pad1)") (class "Default")
      (node (ref "R43") (pin "1") (pinfunction "1_1") (pintype "passive"))
      (node (ref "R45") (pin "1") (pinfunction "1_1") (pintype "passive"))
      (node (ref "SP@2") (pin "1") (pinfunction "1_1") (pintype "passive"))
    )
    (net (code "107") (name "Net-(R100-Pad2)") (class "Default")
      (node (ref "R100") (pin "2") (pinfunction "2_2") (pintype "passive"))
      (node (ref "R4") (pin "2") (pinfunction "2_2") (pintype "passive"))
    )
    (net (code "108") (name "Net-(U$3-+)") (class "Default")
      (node (ref "U$1") (pin "VBAT") (pinfunction "VBAT_VBAT") (pintype "power_in"))
      (node (ref "U$3") (pin "+$1") (pinfunction "+_+$1") (pintype "passive"))
    )
    (net (code "109") (name "Net-(U$4-OE)") (class "Default")
      (node (ref "C40U1") (pin "2") (pinfunction "2_2") (pintype "passive"))
      (node (ref "D1") (pin "A") (pinfunction "A_A") (pintype "passive"))
      (node (ref "R15E8") (pin "1") (pinfunction "1_1") (pintype "passive"))
      (node (ref "U$4") (pin "1") (pinfunction "OE_1") (pintype "bidirectional"))
    )
    (net (code "110") (name "Net-(U$5-ANT)") (class "Default")
      (node (ref "U$5") (pin "P$56") (pinfunction "ANT_P$56") (pintype "bidirectional"))
      (node (ref "X4") (pin "3") (pinfunction "SIGNAL_3") (pintype "passive"))
    )
    (net (code "111") (name "OUT1") (class "Default")
      (node (ref "JP4") (pin "2") (pinfunction "2_2") (pintype "passive"))
      (node (ref "X8") (pin "2") (pinfunction "KL_2") (pintype "passive"))
    )
    (net (code "112") (name "OUT2") (class "Default")
      (node (ref "JP4") (pin "3") (pinfunction "3_3") (pintype "passive"))
      (node (ref "X8") (pin "3") (pinfunction "KL_3") (pintype "passive"))
    )
    (net (code "113") (name "OUT3") (class "Default")
      (node (ref "JP4") (pin "5") (pinfunction "5_5") (pintype "passive"))
      (node (ref "X8") (pin "5") (pinfunction "KL_5") (pintype "passive"))
    )
    (net (code "114") (name "OUT4") (class "Default")
      (node (ref "JP4") (pin "6") (pinfunction "6_6") (pintype "passive"))
      (node (ref "X8") (pin "6") (pinfunction "KL_6") (pintype "passive"))
    )
    (net (code "115") (name "PHY-POW") (class "Default")
      (node (ref "SJ4") (pin "2") (pinfunction "2_2") (pintype "passive"))
      (node (ref "U4") (pin "28") (pinfunction "IO17_28") (pintype "bidirectional"))
    )
    (net (code "116") (name "PHY-POW1") (class "Default")
      (node (ref "SJ4") (pin "1") (pinfunction "1_1") (pintype "passive"))
      (node (ref "SJ6") (pin "1") (pinfunction "1_1") (pintype "passive"))
    )
    (net (code "117") (name "PHY-POW2") (class "Default")
      (node (ref "R15E10") (pin "1") (pinfunction "1_1") (pintype "passive"))
      (node (ref "SJ6") (pin "2") (pinfunction "2_2") (pintype "passive"))
      (node (ref "SV2") (pin "4") (pinfunction "4_4") (pintype "passive"))
    )
    (net (code "118") (name "PM1_ADE") (class "Default")
      (node (ref "ADE9000") (pin "5") (pinfunction "PM1_5") (pintype "bidirectional"))
      (node (ref "ADUM4151") (pin "14") (pinfunction "VOA_14") (pintype "bidirectional"))
    )
    (net (code "119") (name "REF") (class "Default")
      (node (ref "ADE9000") (pin "16") (pinfunction "REF_16") (pintype "bidirectional"))
      (node (ref "C4") (pin "1") (pinfunction "1_1") (pintype "passive"))
      (node (ref "C5") (pin "1") (pinfunction "1_1") (pintype "passive"))
    )
    (net (code "120") (name "REFCLKO{slash}FLASH1") (class "Default")
      (node (ref "SJ3") (pin "2") (pinfunction "2_2") (pintype "passive"))
      (node (ref "U4") (pin "25") (pinfunction "IO0_25") (pintype "bidirectional"))
      (node (ref "X5") (pin "1") (pinfunction "S_1") (pintype "passive"))
    )
    (net (code "121") (name "RESET_ADE") (class "Default")
      (node (ref "ADE9000") (pin "6") (pinfunction "RESET_6") (pintype "bidirectional"))
      (node (ref "ADUM4151") (pin "13") (pinfunction "VOB_13") (pintype "bidirectional"))
      (node (ref "C1") (pin "1") (pinfunction "1_1") (pintype "passive"))
      (node (ref "R3") (pin "1") (pinfunction "1_1") (pintype "passive"))
    )
    (net (code "122") (name "RESET_LORA") (class "Default")
      (node (ref "JP3") (pin "5") (pinfunction "5_5") (pintype "passive"))
    )
    (net (code "123") (name "RX0") (class "Default")
      (node (ref "SV2") (pin "7") (pinfunction "7_7") (pintype "passive"))
      (node (ref "U4") (pin "10") (pinfunction "IO25_10") (pintype "bidirectional"))
    )
    (net (code "124") (name "RX1") (class "Default")
      (node (ref "SV2") (pin "8") (pinfunction "8_8") (pintype "passive"))
      (node (ref "U4") (pin "11") (pinfunction "IO26_11") (pintype "bidirectional"))
    )
    (net (code "125") (name "RXD1-TIME") (class "Default")
      (node (ref "JP2") (pin "5") (pinfunction "5_5") (pintype "passive"))
      (node (ref "U1") (pin "P$13") (pinfunction "B3_P$13") (pintype "bidirectional"))
    )
    (net (code "126") (name "RXD1V8") (class "Default")
      (node (ref "U$5") (pin "P$13") (pinfunction "RXD_P$13") (pintype "output"))
      (node (ref "U1") (pin "P$4") (pinfunction "A3_P$4") (pintype "bidirectional"))
    )
    (net (code "127") (name "RXD_BOOTLOAD") (class "Default")
      (node (ref "JP1") (pin "3") (pinfunction "3_3") (pintype "passive"))
      (node (ref "U4") (pin "34") (pinfunction "RXD0_34") (pintype "bidirectional"))
      (node (ref "X5") (pin "4") (pinfunction "S_4") (pintype "passive"))
    )
    (net (code "128") (name "SARA-RESET") (class "Default")
      (node (ref "JP2") (pin "8") (pinfunction "8_8") (pintype "passive"))
      (node (ref "U1") (pin "P$12") (pinfunction "B4_P$12") (pintype "bidirectional"))
    )
    (net (code "129") (name "SARA-RESET1V8") (class "Default")
      (node (ref "U$5") (pin "P$18") (pinfunction "RESET_IN_P$18") (pintype "input"))
      (node (ref "U1") (pin "P$5") (pinfunction "A4_P$5") (pintype "bidirectional"))
    )
    (net (code "130") (name "SCL") (class "Default")
      (node (ref "H5") (pin "4") (pinfunction "4_4") (pintype "bidirectional"))
      (node (ref "R15E3") (pin "1") (pinfunction "1_1") (pintype "passive"))
      (node (ref "SV1") (pin "4") (pinfunction "4_4") (pintype "passive"))
      (node (ref "SV2") (pin "2") (pinfunction "2_2") (pintype "passive"))
      (node (ref "U4") (pin "9") (pinfunction "IO33_9") (pintype "bidirectional"))
      (node (ref "X1") (pin "2") (pinfunction "S_2") (pintype "passive"))
    )
    (net (code "131") (name "SCL-TIME") (class "Default")
      (node (ref "JP2") (pin "4") (pinfunction "4_4") (pintype "passive"))
      (node (ref "U$1") (pin "SCL") (pinfunction "SCL_SCL") (pintype "bidirectional"))
    )
    (net (code "132") (name "SCLK_ADE") (class "Default")
      (node (ref "ADE9000") (pin "37") (pinfunction "SCLK_37") (pintype "bidirectional"))
      (node (ref "ADUM4151") (pin "18") (pinfunction "SCLK_18") (pintype "bidirectional"))
    )
    (net (code "133") (name "SCLK_LORA") (class "Default")
      (node (ref "JP3") (pin "11") (pinfunction "11_11") (pintype "passive"))
    )
    (net (code "134") (name "SDA") (class "Default")
      (node (ref "H5") (pin "3") (pinfunction "3_3") (pintype "bidirectional"))
      (node (ref "R15E6") (pin "1") (pinfunction "1_1") (pintype "passive"))
      (node (ref "SV1") (pin "1") (pinfunction "1_1") (pintype "passive"))
      (node (ref "SV2") (pin "1") (pinfunction "1_1") (pintype "passive"))
      (node (ref "U4") (pin "8") (pinfunction "IO32_8") (pintype "bidirectional"))
      (node (ref "X1") (pin "3") (pinfunction "S_3") (pintype "passive"))
    )
    (net (code "135") (name "SDA-TIME") (class "Default")
      (node (ref "JP2") (pin "1") (pinfunction "1_1") (pintype "passive"))
      (node (ref "U$1") (pin "SDA") (pinfunction "SDA_SDA") (pintype "bidirectional"))
    )
    (net (code "136") (name "SIM-CLK") (class "Default")
      (node (ref "U$5") (pin "P$38") (pinfunction "SIM_CLK_P$38") (pintype "output"))
    )
    (net (code "137") (name "SIM_CLK") (class "Default")
      (node (ref "C27") (pin "1") (pinfunction "1_1") (pintype "passive"))
      (node (ref "D6") (pin "6") (pinfunction "6_6") (pintype "bidirectional"))
      (node (ref "J9") (pin "C3") (pinfunction "CLK_C3") (pintype "bidirectional"))
    )
    (net (code "138") (name "SIM_IO") (class "Default")
      (node (ref "C28") (pin "1") (pinfunction "1_1") (pintype "passive"))
      (node (ref "D6") (pin "4") (pinfunction "4_4") (pintype "bidirectional"))
      (node (ref "J9") (pin "C7") (pinfunction "IO_C7") (pintype "bidirectional"))
      (node (ref "U$5") (pin "P$39") (pinfunction "SIM_IO_P$39") (pintype "bidirectional"))
    )
    (net (code "139") (name "SIM_RST") (class "Default")
      (node (ref "C26") (pin "1") (pinfunction "1_1") (pintype "passive"))
      (node (ref "D6") (pin "3") (pinfunction "3_3") (pintype "bidirectional"))
      (node (ref "J9") (pin "C2") (pinfunction "RST_C2") (pintype "bidirectional"))
      (node (ref "U$5") (pin "P$40") (pinfunction "SIM_RST_P$40") (pintype "output"))
    )
    (net (code "140") (name "SS_ADE") (class "Default")
      (node (ref "ADE9000") (pin "40") (pinfunction "SS_40") (pintype "bidirectional"))
      (node (ref "ADUM4151") (pin "15") (pinfunction "SSS_15") (pintype "bidirectional"))
    )
    (net (code "141") (name "SS_LORA") (class "Default")
      (node (ref "JP3") (pin "10") (pinfunction "10_10") (pintype "passive"))
    )
    (net (code "142") (name "TX-EN") (class "Default")
      (node (ref "SV2") (pin "5") (pinfunction "5_5") (pintype "passive"))
      (node (ref "U4") (pin "33") (pinfunction "IO21_33") (pintype "bidirectional"))
    )
    (net (code "143") (name "TX0") (class "Default")
      (node (ref "SV2") (pin "6") (pinfunction "6_6") (pintype "passive"))
      (node (ref "U4") (pin "31") (pinfunction "IO19_31") (pintype "bidirectional"))
    )
    (net (code "144") (name "TX1") (class "Default")
      (node (ref "SV2") (pin "3") (pinfunction "3_3") (pintype "passive"))
      (node (ref "U4") (pin "36") (pinfunction "IO22_36") (pintype "bidirectional"))
    )
    (net (code "145") (name "TXD1-TIME") (class "Default")
      (node (ref "JP2") (pin "6") (pinfunction "6_6") (pintype "passive"))
      (node (ref "U1") (pin "P$16") (pinfunction "B1_P$16") (pintype "bidirectional"))
    )
    (net (code "146") (name "TXD1V8") (class "Default")
      (node (ref "U$5") (pin "P$12") (pinfunction "TXD_P$12") (pintype "input"))
      (node (ref "U1") (pin "P$1") (pinfunction "A1_P$1") (pintype "bidirectional"))
    )
    (net (code "147") (name "TXD_BOOTLOAD") (class "Default")
      (node (ref "JP1") (pin "1") (pinfunction "1_1") (pintype "passive"))
      (node (ref "U4") (pin "35") (pinfunction "TXD0_35") (pintype "bidirectional"))
      (node (ref "X5") (pin "3") (pinfunction "S_3") (pintype "passive"))
    )
    (net (code "148") (name "VAN") (class "Default")
      (node (ref "ADE9000") (pin "19") (pinfunction "VAN_19") (pintype "bidirectional"))
      (node (ref "C101") (pin "1") (pinfunction "1_1") (pintype "passive"))
      (node (ref "C200") (pin "2") (pinfunction "2_2") (pintype "passive"))
      (node (ref "R200") (pin "1") (pinfunction "1_1") (pintype "passive"))
    )
    (net (code "149") (name "VAP") (class "Default")
      (node (ref "ADE9000") (pin "20") (pinfunction "VAP_20") (pintype "bidirectional"))
      (node (ref "C100") (pin "2") (pinfunction "2_2") (pintype "passive"))
      (node (ref "C101") (pin "2") (pinfunction "2_2") (pintype "passive"))
      (node (ref "R100") (pin "1") (pinfunction "1_1") (pintype "passive"))
      (node (ref "R104") (pin "1") (pinfunction "1_1") (pintype "passive"))
    )
    (net (code "150") (name "VBN") (class "Default")
      (node (ref "ADE9000") (pin "21") (pinfunction "VBN_21") (pintype "bidirectional"))
      (node (ref "C12") (pin "2") (pinfunction "2_2") (pintype "passive"))
      (node (ref "C14") (pin "1") (pinfunction "1_1") (pintype "passive"))
      (node (ref "R2") (pin "1") (pinfunction "1_1") (pintype "passive"))
    )
    (net (code "151") (name "VBP") (class "Default")
      (node (ref "ADE9000") (pin "22") (pinfunction "VBP_22") (pintype "bidirectional"))
      (node (ref "C13") (pin "2") (pinfunction "2_2") (pintype "passive"))
      (node (ref "C14") (pin "2") (pinfunction "2_2") (pintype "passive"))
      (node (ref "R5") (pin "1") (pinfunction "1_1") (pintype "passive"))
      (node (ref "R7") (pin "1") (pinfunction "1_1") (pintype "passive"))
    )
    (net (code "152") (name "VCC-IO1{slash}4") (class "Default")
      (node (ref "JP4") (pin "4") (pinfunction "4_4") (pintype "passive"))
      (node (ref "X8") (pin "4") (pinfunction "KL_4") (pintype "passive"))
    )
    (net (code "153") (name "VCN") (class "Default")
      (node (ref "ADE9000") (pin "23") (pinfunction "VCN_23") (pintype "bidirectional"))
      (node (ref "C15") (pin "2") (pinfunction "2_2") (pintype "passive"))
      (node (ref "C17") (pin "1") (pinfunction "1_1") (pintype "passive"))
      (node (ref "R10") (pin "1") (pinfunction "1_1") (pintype "passive"))
    )
    (net (code "154") (name "VCP") (class "Default")
      (node (ref "ADE9000") (pin "24") (pinfunction "VCP_24") (pintype "bidirectional"))
      (node (ref "C16") (pin "2") (pinfunction "2_2") (pintype "passive"))
      (node (ref "C17") (pin "2") (pinfunction "2_2") (pintype "passive"))
      (node (ref "R11") (pin "1") (pinfunction "1_1") (pintype "passive"))
      (node (ref "R13") (pin "1") (pinfunction "1_1") (pintype "passive"))
    )
    (net (code "155") (name "VL1") (class "Default")
      (node (ref "FUSE2") (pin "2") (pinfunction "2_2") (pintype "passive"))
      (node (ref "X2") (pin "2") (pinfunction "KL_2") (pintype "passive"))
    )
    (net (code "156") (name "VL2") (class "Default")
      (node (ref "FUSE1") (pin "2") (pinfunction "2_2") (pintype "passive"))
      (node (ref "X2") (pin "3") (pinfunction "KL_3") (pintype "passive"))
    )
    (net (code "157") (name "VL2-FUSE") (class "Default")
      (node (ref "FUSE1") (pin "1") (pinfunction "1_1") (pintype "passive"))
      (node (ref "L2") (pin "1") (pinfunction "1_1") (pintype "passive"))
      (node (ref "SJ2") (pin "1") (pinfunction "1_1") (pintype "passive"))
    )
    (net (code "158") (name "VL3") (class "Default")
      (node (ref "FUSE3") (pin "2") (pinfunction "2_2") (pintype "passive"))
      (node (ref "X2") (pin "4") (pinfunction "KL_4") (pintype "passive"))
    )
    (net (code "159") (name "VSIM") (class "Default")
      (node (ref "C29") (pin "1") (pinfunction "1_1") (pintype "passive"))
      (node (ref "C30") (pin "1") (pinfunction "1_1") (pintype "passive"))
      (node (ref "D6") (pin "1") (pinfunction "1_1") (pintype "bidirectional"))
      (node (ref "J9") (pin "C1") (pinfunction "VCC_C1") (pintype "bidirectional"))
      (node (ref "U$5") (pin "P$41") (pinfunction "VSIM_P$41") (pintype "output"))
    )
    (net (code "160") (name "ZEROCROSS_ADE") (class "Default")
      (node (ref "ADE9000") (pin "35") (pinfunction "CF3_35") (pintype "bidirectional"))
      (node (ref "ADUM6402-2") (pin "12") (pinfunction "VIC_12") (pintype "bidirectional"))
    )
    (net (code "161") (name "unconnected-(ADE9000-CF2-Pad34)") (class "Default")
      (node (ref "ADE9000") (pin "34") (pinfunction "CF2_34") (pintype "bidirectional"))
    )
    (net (code "162") (name "unconnected-(ADE9000-CF4-Pad36)") (class "Default")
      (node (ref "ADE9000") (pin "36") (pinfunction "CF4_36") (pintype "bidirectional"))
    )
    (net (code "163") (name "unconnected-(ADE9000-IRQ0-Pad31)") (class "Default")
      (node (ref "ADE9000") (pin "31") (pinfunction "IRQ0_31") (pintype "bidirectional"))
    )
    (net (code "164") (name "unconnected-(ADUM6402-2-VOA-Pad14)") (class "Default")
      (node (ref "ADUM6402-2") (pin "14") (pinfunction "VOA_14") (pintype "bidirectional"))
    )
    (net (code "165") (name "unconnected-(ADUM6402-2-VOB-Pad13)") (class "Default")
      (node (ref "ADUM6402-2") (pin "13") (pinfunction "VOB_13") (pintype "bidirectional"))
    )
    (net (code "166") (name "unconnected-(J9-VPP-PadC6)") (class "Default")
      (node (ref "J9") (pin "C6") (pinfunction "VPP_C6") (pintype "bidirectional"))
    )
    (net (code "167") (name "unconnected-(JP2-Pad2)") (class "Default")
      (node (ref "JP2") (pin "2") (pinfunction "2_2") (pintype "passive"))
    )
    (net (code "168") (name "unconnected-(JP2-Pad10)") (class "Default")
      (node (ref "JP2") (pin "10") (pinfunction "10_10") (pintype "passive"))
    )
    (net (code "169") (name "unconnected-(JP3-Pad1)") (class "Default")
      (node (ref "JP3") (pin "1") (pinfunction "1_1") (pintype "passive"))
    )
    (net (code "170") (name "unconnected-(JP3-Pad2)") (class "Default")
      (node (ref "JP3") (pin "2") (pinfunction "2_2") (pintype "passive"))
    )
    (net (code "171") (name "unconnected-(JP3-Pad4)") (class "Default")
      (node (ref "JP3") (pin "4") (pinfunction "4_4") (pintype "passive"))
    )
    (net (code "172") (name "unconnected-(JP3-Pad7)") (class "Default")
      (node (ref "JP3") (pin "7") (pinfunction "7_7") (pintype "passive"))
    )
    (net (code "173") (name "unconnected-(JP3-Pad9)") (class "Default")
      (node (ref "JP3") (pin "9") (pinfunction "9_9") (pintype "passive"))
    )
    (net (code "174") (name "unconnected-(JP3-Pad17)") (class "Default")
      (node (ref "JP3") (pin "17") (pinfunction "17_17") (pintype "passive"))
    )
    (net (code "175") (name "unconnected-(JP3-Pad18)") (class "Default")
      (node (ref "JP3") (pin "18") (pinfunction "18_18") (pintype "passive"))
    )
    (net (code "176") (name "unconnected-(SV1-Pad2)") (class "Default")
      (node (ref "SV1") (pin "2") (pinfunction "2_2") (pintype "passive"))
    )
    (net (code "177") (name "unconnected-(SV1-Pad10)") (class "Default")
      (node (ref "SV1") (pin "10") (pinfunction "10_10") (pintype "passive"))
    )
    (net (code "178") (name "unconnected-(SV3-Pad1)") (class "Default")
      (node (ref "SV3") (pin "1") (pinfunction "1_1") (pintype "passive"))
    )
    (net (code "179") (name "unconnected-(SV3-Pad2)") (class "Default")
      (node (ref "SV3") (pin "2") (pinfunction "2_2") (pintype "passive"))
    )
    (net (code "180") (name "unconnected-(SV3-Pad3)") (class "Default")
      (node (ref "SV3") (pin "3") (pinfunction "3_3") (pintype "passive"))
    )
    (net (code "181") (name "unconnected-(SV3-Pad4)") (class "Default")
      (node (ref "SV3") (pin "4") (pinfunction "4_4") (pintype "passive"))
    )
    (net (code "182") (name "unconnected-(SV3-Pad5)") (class "Default")
      (node (ref "SV3") (pin "5") (pinfunction "5_5") (pintype "passive"))
    )
    (net (code "183") (name "unconnected-(SV3-Pad6)") (class "Default")
      (node (ref "SV3") (pin "6") (pinfunction "6_6") (pintype "passive"))
    )
    (net (code "184") (name "unconnected-(SV3-Pad7)") (class "Default")
      (node (ref "SV3") (pin "7") (pinfunction "7_7") (pintype "passive"))
    )
    (net (code "185") (name "unconnected-(SV3-Pad8)") (class "Default")
      (node (ref "SV3") (pin "8") (pinfunction "8_8") (pintype "passive"))
    )
    (net (code "186") (name "unconnected-(SV3-Pad9)") (class "Default")
      (node (ref "SV3") (pin "9") (pinfunction "9_9") (pintype "passive"))
    )
    (net (code "187") (name "unconnected-(SV3-Pad10)") (class "Default")
      (node (ref "SV3") (pin "10") (pinfunction "10_10") (pintype "passive"))
    )
    (net (code "188") (name "unconnected-(SV3-Pad11)") (class "Default")
      (node (ref "SV3") (pin "11") (pinfunction "11_11") (pintype "passive"))
    )
    (net (code "189") (name "unconnected-(SV3-Pad12)") (class "Default")
      (node (ref "SV3") (pin "12") (pinfunction "12_12") (pintype "passive"))
    )
    (net (code "190") (name "unconnected-(SV3-Pad13)") (class "Default")
      (node (ref "SV3") (pin "13") (pinfunction "13_13") (pintype "passive"))
    )
    (net (code "191") (name "unconnected-(SV3-Pad14)") (class "Default")
      (node (ref "SV3") (pin "14") (pinfunction "14_14") (pintype "passive"))
    )
    (net (code "192") (name "unconnected-(SV3-Pad15)") (class "Default")
      (node (ref "SV3") (pin "15") (pinfunction "15_15") (pintype "passive"))
    )
    (net (code "193") (name "unconnected-(SV3-Pad16)") (class "Default")
      (node (ref "SV3") (pin "16") (pinfunction "16_16") (pintype "passive"))
    )
    (net (code "194") (name "unconnected-(SV3-Pad17)") (class "Default")
      (node (ref "SV3") (pin "17") (pinfunction "17_17") (pintype "passive"))
    )
    (net (code "195") (name "unconnected-(SV3-Pad18)") (class "Default")
      (node (ref "SV3") (pin "18") (pinfunction "18_18") (pintype "passive"))
    )
    (net (code "196") (name "unconnected-(SV3-Pad19)") (class "Default")
      (node (ref "SV3") (pin "19") (pinfunction "19_19") (pintype "passive"))
    )
    (net (code "197") (name "unconnected-(SV3-Pad20)") (class "Default")
      (node (ref "SV3") (pin "20") (pinfunction "20_20") (pintype "passive"))
    )
    (net (code "198") (name "unconnected-(SV4-Pad1)") (class "Default")
      (node (ref "SV4") (pin "1") (pinfunction "1_1") (pintype "passive"))
    )
    (net (code "199") (name "unconnected-(SV4-Pad2)") (class "Default")
      (node (ref "SV4") (pin "2") (pinfunction "2_2") (pintype "passive"))
    )
    (net (code "200") (name "unconnected-(SV4-Pad3)") (class "Default")
      (node (ref "SV4") (pin "3") (pinfunction "3_3") (pintype "passive"))
    )
    (net (code "201") (name "unconnected-(SV4-Pad4)") (class "Default")
      (node (ref "SV4") (pin "4") (pinfunction "4_4") (pintype "passive"))
    )
    (net (code "202") (name "unconnected-(SV4-Pad5)") (class "Default")
      (node (ref "SV4") (pin "5") (pinfunction "5_5") (pintype "passive"))
    )
    (net (code "203") (name "unconnected-(SV4-Pad6)") (class "Default")
      (node (ref "SV4") (pin "6") (pinfunction "6_6") (pintype "passive"))
    )
    (net (code "204") (name "unconnected-(SV4-Pad7)") (class "Default")
      (node (ref "SV4") (pin "7") (pinfunction "7_7") (pintype "passive"))
    )
    (net (code "205") (name "unconnected-(SV4-Pad8)") (class "Default")
      (node (ref "SV4") (pin "8") (pinfunction "8_8") (pintype "passive"))
    )
    (net (code "206") (name "unconnected-(SV4-Pad9)") (class "Default")
      (node (ref "SV4") (pin "9") (pinfunction "9_9") (pintype "passive"))
    )
    (net (code "207") (name "unconnected-(SV4-Pad10)") (class "Default")
      (node (ref "SV4") (pin "10") (pinfunction "10_10") (pintype "passive"))
    )
    (net (code "208") (name "unconnected-(SV4-Pad11)") (class "Default")
      (node (ref "SV4") (pin "11") (pinfunction "11_11") (pintype "passive"))
    )
    (net (code "209") (name "unconnected-(SV4-Pad12)") (class "Default")
      (node (ref "SV4") (pin "12") (pinfunction "12_12") (pintype "passive"))
    )
    (net (code "210") (name "unconnected-(SV4-Pad13)") (class "Default")
      (node (ref "SV4") (pin "13") (pinfunction "13_13") (pintype "passive"))
    )
    (net (code "211") (name "unconnected-(SV4-Pad14)") (class "Default")
      (node (ref "SV4") (pin "14") (pinfunction "14_14") (pintype "passive"))
    )
    (net (code "212") (name "unconnected-(SV4-Pad15)") (class "Default")
      (node (ref "SV4") (pin "15") (pinfunction "15_15") (pintype "passive"))
    )
    (net (code "213") (name "unconnected-(SV4-Pad16)") (class "Default")
      (node (ref "SV4") (pin "16") (pinfunction "16_16") (pintype "passive"))
    )
    (net (code "214") (name "unconnected-(SV4-Pad17)") (class "Default")
      (node (ref "SV4") (pin "17") (pinfunction "17_17") (pintype "passive"))
    )
    (net (code "215") (name "unconnected-(SV4-Pad18)") (class "Default")
      (node (ref "SV4") (pin "18") (pinfunction "18_18") (pintype "passive"))
    )
    (net (code "216") (name "unconnected-(SV4-Pad19)") (class "Default")
      (node (ref "SV4") (pin "19") (pinfunction "19_19") (pintype "passive"))
    )
    (net (code "217") (name "unconnected-(SV4-Pad20)") (class "Default")
      (node (ref "SV4") (pin "20") (pinfunction "20_20") (pintype "passive"))
    )
    (net (code "218") (name "unconnected-(SV5-Pad1)") (class "Default")
      (node (ref "SV5") (pin "1") (pinfunction "1_1") (pintype "passive"))
    )
    (net (code "219") (name "unconnected-(SV5-Pad2)") (class "Default")
      (node (ref "SV5") (pin "2") (pinfunction "2_2") (pintype "passive"))
    )
    (net (code "220") (name "unconnected-(SV5-Pad3)") (class "Default")
      (node (ref "SV5") (pin "3") (pinfunction "3_3") (pintype "passive"))
    )
    (net (code "221") (name "unconnected-(SV5-Pad4)") (class "Default")
      (node (ref "SV5") (pin "4") (pinfunction "4_4") (pintype "passive"))
    )
    (net (code "222") (name "unconnected-(SV5-Pad5)") (class "Default")
      (node (ref "SV5") (pin "5") (pinfunction "5_5") (pintype "passive"))
    )
    (net (code "223") (name "unconnected-(SV5-Pad6)") (class "Default")
      (node (ref "SV5") (pin "6") (pinfunction "6_6") (pintype "passive"))
    )
    (net (code "224") (name "unconnected-(SV5-Pad7)") (class "Default")
      (node (ref "SV5") (pin "7") (pinfunction "7_7") (pintype "passive"))
    )
    (net (code "225") (name "unconnected-(SV5-Pad8)") (class "Default")
      (node (ref "SV5") (pin "8") (pinfunction "8_8") (pintype "passive"))
    )
    (net (code "226") (name "unconnected-(SV5-Pad9)") (class "Default")
      (node (ref "SV5") (pin "9") (pinfunction "9_9") (pintype "passive"))
    )
    (net (code "227") (name "unconnected-(SV5-Pad10)") (class "Default")
      (node (ref "SV5") (pin "10") (pinfunction "10_10") (pintype "passive"))
    )
    (net (code "228") (name "unconnected-(SV5-Pad11)") (class "Default")
      (node (ref "SV5") (pin "11") (pinfunction "11_11") (pintype "passive"))
    )
    (net (code "229") (name "unconnected-(SV5-Pad12)") (class "Default")
      (node (ref "SV5") (pin "12") (pinfunction "12_12") (pintype "passive"))
    )
    (net (code "230") (name "unconnected-(SV5-Pad13)") (class "Default")
      (node (ref "SV5") (pin "13") (pinfunction "13_13") (pintype "passive"))
    )
    (net (code "231") (name "unconnected-(SV5-Pad14)") (class "Default")
      (node (ref "SV5") (pin "14") (pinfunction "14_14") (pintype "passive"))
    )
    (net (code "232") (name "unconnected-(SV5-Pad15)") (class "Default")
      (node (ref "SV5") (pin "15") (pinfunction "15_15") (pintype "passive"))
    )
    (net (code "233") (name "unconnected-(SV5-Pad16)") (class "Default")
      (node (ref "SV5") (pin "16") (pinfunction "16_16") (pintype "passive"))
    )
    (net (code "234") (name "unconnected-(SV5-Pad17)") (class "Default")
      (node (ref "SV5") (pin "17") (pinfunction "17_17") (pintype "passive"))
    )
    (net (code "235") (name "unconnected-(SV5-Pad18)") (class "Default")
      (node (ref "SV5") (pin "18") (pinfunction "18_18") (pintype "passive"))
    )
    (net (code "236") (name "unconnected-(SV5-Pad19)") (class "Default")
      (node (ref "SV5") (pin "19") (pinfunction "19_19") (pintype "passive"))
    )
    (net (code "237") (name "unconnected-(SV5-Pad20)") (class "Default")
      (node (ref "SV5") (pin "20") (pinfunction "20_20") (pintype "passive"))
    )
    (net (code "238") (name "unconnected-(SV6-Pad1)") (class "Default")
      (node (ref "SV6") (pin "1") (pinfunction "1_1") (pintype "passive"))
    )
    (net (code "239") (name "unconnected-(SV6-Pad2)") (class "Default")
      (node (ref "SV6") (pin "2") (pinfunction "2_2") (pintype "passive"))
    )
    (net (code "240") (name "unconnected-(SV6-Pad3)") (class "Default")
      (node (ref "SV6") (pin "3") (pinfunction "3_3") (pintype "passive"))
    )
    (net (code "241") (name "unconnected-(SV6-Pad4)") (class "Default")
      (node (ref "SV6") (pin "4") (pinfunction "4_4") (pintype "passive"))
    )
    (net (code "242") (name "unconnected-(SV6-Pad5)") (class "Default")
      (node (ref "SV6") (pin "5") (pinfunction "5_5") (pintype "passive"))
    )
    (net (code "243") (name "unconnected-(SV6-Pad6)") (class "Default")
      (node (ref "SV6") (pin "6") (pinfunction "6_6") (pintype "passive"))
    )
    (net (code "244") (name "unconnected-(SV6-Pad7)") (class "Default")
      (node (ref "SV6") (pin "7") (pinfunction "7_7") (pintype "passive"))
    )
    (net (code "245") (name "unconnected-(SV6-Pad8)") (class "Default")
      (node (ref "SV6") (pin "8") (pinfunction "8_8") (pintype "passive"))
    )
    (net (code "246") (name "unconnected-(SV6-Pad9)") (class "Default")
      (node (ref "SV6") (pin "9") (pinfunction "9_9") (pintype "passive"))
    )
    (net (code "247") (name "unconnected-(SV6-Pad10)") (class "Default")
      (node (ref "SV6") (pin "10") (pinfunction "10_10") (pintype "passive"))
    )
    (net (code "248") (name "unconnected-(SV6-Pad11)") (class "Default")
      (node (ref "SV6") (pin "11") (pinfunction "11_11") (pintype "passive"))
    )
    (net (code "249") (name "unconnected-(SV6-Pad12)") (class "Default")
      (node (ref "SV6") (pin "12") (pinfunction "12_12") (pintype "passive"))
    )
    (net (code "250") (name "unconnected-(SV6-Pad13)") (class "Default")
      (node (ref "SV6") (pin "13") (pinfunction "13_13") (pintype "passive"))
    )
    (net (code "251") (name "unconnected-(SV6-Pad14)") (class "Default")
      (node (ref "SV6") (pin "14") (pinfunction "14_14") (pintype "passive"))
    )
    (net (code "252") (name "unconnected-(SV6-Pad15)") (class "Default")
      (node (ref "SV6") (pin "15") (pinfunction "15_15") (pintype "passive"))
    )
    (net (code "253") (name "unconnected-(SV6-Pad16)") (class "Default")
      (node (ref "SV6") (pin "16") (pinfunction "16_16") (pintype "passive"))
    )
    (net (code "254") (name "unconnected-(SV6-Pad17)") (class "Default")
      (node (ref "SV6") (pin "17") (pinfunction "17_17") (pintype "passive"))
    )
    (net (code "255") (name "unconnected-(SV6-Pad18)") (class "Default")
      (node (ref "SV6") (pin "18") (pinfunction "18_18") (pintype "passive"))
    )
    (net (code "256") (name "unconnected-(SV6-Pad19)") (class "Default")
      (node (ref "SV6") (pin "19") (pinfunction "19_19") (pintype "passive"))
    )
    (net (code "257") (name "unconnected-(SV6-Pad20)") (class "Default")
      (node (ref "SV6") (pin "20") (pinfunction "20_20") (pintype "passive"))
    )
    (net (code "258") (name "unconnected-(SV7-Pad1)") (class "Default")
      (node (ref "SV7") (pin "1") (pinfunction "1_1") (pintype "passive"))
    )
    (net (code "259") (name "unconnected-(SV7-Pad2)") (class "Default")
      (node (ref "SV7") (pin "2") (pinfunction "2_2") (pintype "passive"))
    )
    (net (code "260") (name "unconnected-(SV7-Pad3)") (class "Default")
      (node (ref "SV7") (pin "3") (pinfunction "3_3") (pintype "passive"))
    )
    (net (code "261") (name "unconnected-(SV7-Pad4)") (class "Default")
      (node (ref "SV7") (pin "4") (pinfunction "4_4") (pintype "passive"))
    )
    (net (code "262") (name "unconnected-(SV7-Pad5)") (class "Default")
      (node (ref "SV7") (pin "5") (pinfunction "5_5") (pintype "passive"))
    )
    (net (code "263") (name "unconnected-(SV7-Pad6)") (class "Default")
      (node (ref "SV7") (pin "6") (pinfunction "6_6") (pintype "passive"))
    )
    (net (code "264") (name "unconnected-(SV7-Pad7)") (class "Default")
      (node (ref "SV7") (pin "7") (pinfunction "7_7") (pintype "passive"))
    )
    (net (code "265") (name "unconnected-(SV7-Pad8)") (class "Default")
      (node (ref "SV7") (pin "8") (pinfunction "8_8") (pintype "passive"))
    )
    (net (code "266") (name "unconnected-(SV7-Pad9)") (class "Default")
      (node (ref "SV7") (pin "9") (pinfunction "9_9") (pintype "passive"))
    )
    (net (code "267") (name "unconnected-(SV7-Pad10)") (class "Default")
      (node (ref "SV7") (pin "10") (pinfunction "10_10") (pintype "passive"))
    )
    (net (code "268") (name "unconnected-(SV7-Pad11)") (class "Default")
      (node (ref "SV7") (pin "11") (pinfunction "11_11") (pintype "passive"))
    )
    (net (code "269") (name "unconnected-(SV7-Pad12)") (class "Default")
      (node (ref "SV7") (pin "12") (pinfunction "12_12") (pintype "passive"))
    )
    (net (code "270") (name "unconnected-(SV7-Pad13)") (class "Default")
      (node (ref "SV7") (pin "13") (pinfunction "13_13") (pintype "passive"))
    )
    (net (code "271") (name "unconnected-(SV7-Pad14)") (class "Default")
      (node (ref "SV7") (pin "14") (pinfunction "14_14") (pintype "passive"))
    )
    (net (code "272") (name "unconnected-(SV7-Pad15)") (class "Default")
      (node (ref "SV7") (pin "15") (pinfunction "15_15") (pintype "passive"))
    )
    (net (code "273") (name "unconnected-(SV7-Pad16)") (class "Default")
      (node (ref "SV7") (pin "16") (pinfunction "16_16") (pintype "passive"))
    )
    (net (code "274") (name "unconnected-(SV8-Pad1)") (class "Default")
      (node (ref "SV8") (pin "1") (pinfunction "1_1") (pintype "passive"))
    )
    (net (code "275") (name "unconnected-(SV8-Pad2)") (class "Default")
      (node (ref "SV8") (pin "2") (pinfunction "2_2") (pintype "passive"))
    )
    (net (code "276") (name "unconnected-(SV8-Pad3)") (class "Default")
      (node (ref "SV8") (pin "3") (pinfunction "3_3") (pintype "passive"))
    )
    (net (code "277") (name "unconnected-(SV8-Pad4)") (class "Default")
      (node (ref "SV8") (pin "4") (pinfunction "4_4") (pintype "passive"))
    )
    (net (code "278") (name "unconnected-(SV8-Pad5)") (class "Default")
      (node (ref "SV8") (pin "5") (pinfunction "5_5") (pintype "passive"))
    )
    (net (code "279") (name "unconnected-(SV8-Pad6)") (class "Default")
      (node (ref "SV8") (pin "6") (pinfunction "6_6") (pintype "passive"))
    )
    (net (code "280") (name "unconnected-(SV8-Pad7)") (class "Default")
      (node (ref "SV8") (pin "7") (pinfunction "7_7") (pintype "passive"))
    )
    (net (code "281") (name "unconnected-(SV8-Pad8)") (class "Default")
      (node (ref "SV8") (pin "8") (pinfunction "8_8") (pintype "passive"))
    )
    (net (code "282") (name "unconnected-(SV8-Pad9)") (class "Default")
      (node (ref "SV8") (pin "9") (pinfunction "9_9") (pintype "passive"))
    )
    (net (code "283") (name "unconnected-(SV8-Pad10)") (class "Default")
      (node (ref "SV8") (pin "10") (pinfunction "10_10") (pintype "passive"))
    )
    (net (code "284") (name "unconnected-(SV8-Pad11)") (class "Default")
      (node (ref "SV8") (pin "11") (pinfunction "11_11") (pintype "passive"))
    )
    (net (code "285") (name "unconnected-(SV8-Pad12)") (class "Default")
      (node (ref "SV8") (pin "12") (pinfunction "12_12") (pintype "passive"))
    )
    (net (code "286") (name "unconnected-(SV8-Pad13)") (class "Default")
      (node (ref "SV8") (pin "13") (pinfunction "13_13") (pintype "passive"))
    )
    (net (code "287") (name "unconnected-(SV8-Pad14)") (class "Default")
      (node (ref "SV8") (pin "14") (pinfunction "14_14") (pintype "passive"))
    )
    (net (code "288") (name "unconnected-(SV8-Pad15)") (class "Default")
      (node (ref "SV8") (pin "15") (pinfunction "15_15") (pintype "passive"))
    )
    (net (code "289") (name "unconnected-(SV8-Pad16)") (class "Default")
      (node (ref "SV8") (pin "16") (pinfunction "16_16") (pintype "passive"))
    )
    (net (code "290") (name "unconnected-(SV8-Pad17)") (class "Default")
      (node (ref "SV8") (pin "17") (pinfunction "17_17") (pintype "passive"))
    )
    (net (code "291") (name "unconnected-(SV8-Pad18)") (class "Default")
      (node (ref "SV8") (pin "18") (pinfunction "18_18") (pintype "passive"))
    )
    (net (code "292") (name "unconnected-(SV8-Pad19)") (class "Default")
      (node (ref "SV8") (pin "19") (pinfunction "19_19") (pintype "passive"))
    )
    (net (code "293") (name "unconnected-(SV8-Pad20)") (class "Default")
      (node (ref "SV8") (pin "20") (pinfunction "20_20") (pintype "passive"))
    )
    (net (code "294") (name "unconnected-(SV9-Pad1)") (class "Default")
      (node (ref "SV9") (pin "1") (pinfunction "1_1") (pintype "passive"))
    )
    (net (code "295") (name "unconnected-(SV9-Pad2)") (class "Default")
      (node (ref "SV9") (pin "2") (pinfunction "2_2") (pintype "passive"))
    )
    (net (code "296") (name "unconnected-(SV9-Pad3)") (class "Default")
      (node (ref "SV9") (pin "3") (pinfunction "3_3") (pintype "passive"))
    )
    (net (code "297") (name "unconnected-(SV9-Pad4)") (class "Default")
      (node (ref "SV9") (pin "4") (pinfunction "4_4") (pintype "passive"))
    )
    (net (code "298") (name "unconnected-(SV9-Pad5)") (class "Default")
      (node (ref "SV9") (pin "5") (pinfunction "5_5") (pintype "passive"))
    )
    (net (code "299") (name "unconnected-(SV9-Pad6)") (class "Default")
      (node (ref "SV9") (pin "6") (pinfunction "6_6") (pintype "passive"))
    )
    (net (code "300") (name "unconnected-(SV9-Pad7)") (class "Default")
      (node (ref "SV9") (pin "7") (pinfunction "7_7") (pintype "passive"))
    )
    (net (code "301") (name "unconnected-(SV9-Pad8)") (class "Default")
      (node (ref "SV9") (pin "8") (pinfunction "8_8") (pintype "passive"))
    )
    (net (code "302") (name "unconnected-(SV9-Pad9)") (class "Default")
      (node (ref "SV9") (pin "9") (pinfunction "9_9") (pintype "passive"))
    )
    (net (code "303") (name "unconnected-(SV9-Pad10)") (class "Default")
      (node (ref "SV9") (pin "10") (pinfunction "10_10") (pintype "passive"))
    )
    (net (code "304") (name "unconnected-(SV9-Pad11)") (class "Default")
      (node (ref "SV9") (pin "11") (pinfunction "11_11") (pintype "passive"))
    )
    (net (code "305") (name "unconnected-(SV9-Pad12)") (class "Default")
      (node (ref "SV9") (pin "12") (pinfunction "12_12") (pintype "passive"))
    )
    (net (code "306") (name "unconnected-(SV9-Pad13)") (class "Default")
      (node (ref "SV9") (pin "13") (pinfunction "13_13") (pintype "passive"))
    )
    (net (code "307") (name "unconnected-(SV9-Pad14)") (class "Default")
      (node (ref "SV9") (pin "14") (pinfunction "14_14") (pintype "passive"))
    )
    (net (code "308") (name "unconnected-(SV9-Pad15)") (class "Default")
      (node (ref "SV9") (pin "15") (pinfunction "15_15") (pintype "passive"))
    )
    (net (code "309") (name "unconnected-(SV9-Pad16)") (class "Default")
      (node (ref "SV9") (pin "16") (pinfunction "16_16") (pintype "passive"))
    )
    (net (code "310") (name "unconnected-(SV9-Pad17)") (class "Default")
      (node (ref "SV9") (pin "17") (pinfunction "17_17") (pintype "passive"))
    )
    (net (code "311") (name "unconnected-(SV9-Pad18)") (class "Default")
      (node (ref "SV9") (pin "18") (pinfunction "18_18") (pintype "passive"))
    )
    (net (code "312") (name "unconnected-(SV9-Pad19)") (class "Default")
      (node (ref "SV9") (pin "19") (pinfunction "19_19") (pintype "passive"))
    )
    (net (code "313") (name "unconnected-(SV9-Pad20)") (class "Default")
      (node (ref "SV9") (pin "20") (pinfunction "20_20") (pintype "passive"))
    )
    (net (code "314") (name "unconnected-(SV10-Pad1)") (class "Default")
      (node (ref "SV10") (pin "1") (pinfunction "1_1") (pintype "passive"))
    )
    (net (code "315") (name "unconnected-(SV10-Pad2)") (class "Default")
      (node (ref "SV10") (pin "2") (pinfunction "2_2") (pintype "passive"))
    )
    (net (code "316") (name "unconnected-(SV10-Pad3)") (class "Default")
      (node (ref "SV10") (pin "3") (pinfunction "3_3") (pintype "passive"))
    )
    (net (code "317") (name "unconnected-(SV10-Pad4)") (class "Default")
      (node (ref "SV10") (pin "4") (pinfunction "4_4") (pintype "passive"))
    )
    (net (code "318") (name "unconnected-(SV10-Pad5)") (class "Default")
      (node (ref "SV10") (pin "5") (pinfunction "5_5") (pintype "passive"))
    )
    (net (code "319") (name "unconnected-(SV10-Pad6)") (class "Default")
      (node (ref "SV10") (pin "6") (pinfunction "6_6") (pintype "passive"))
    )
    (net (code "320") (name "unconnected-(SV10-Pad7)") (class "Default")
      (node (ref "SV10") (pin "7") (pinfunction "7_7") (pintype "passive"))
    )
    (net (code "321") (name "unconnected-(SV10-Pad8)") (class "Default")
      (node (ref "SV10") (pin "8") (pinfunction "8_8") (pintype "passive"))
    )
    (net (code "322") (name "unconnected-(SV10-Pad9)") (class "Default")
      (node (ref "SV10") (pin "9") (pinfunction "9_9") (pintype "passive"))
    )
    (net (code "323") (name "unconnected-(SV10-Pad10)") (class "Default")
      (node (ref "SV10") (pin "10") (pinfunction "10_10") (pintype "passive"))
    )
    (net (code "324") (name "unconnected-(SV10-Pad11)") (class "Default")
      (node (ref "SV10") (pin "11") (pinfunction "11_11") (pintype "passive"))
    )
    (net (code "325") (name "unconnected-(SV10-Pad12)") (class "Default")
      (node (ref "SV10") (pin "12") (pinfunction "12_12") (pintype "passive"))
    )
    (net (code "326") (name "unconnected-(SV10-Pad13)") (class "Default")
      (node (ref "SV10") (pin "13") (pinfunction "13_13") (pintype "passive"))
    )
    (net (code "327") (name "unconnected-(SV10-Pad14)") (class "Default")
      (node (ref "SV10") (pin "14") (pinfunction "14_14") (pintype "passive"))
    )
    (net (code "328") (name "unconnected-(SV10-Pad15)") (class "Default")
      (node (ref "SV10") (pin "15") (pinfunction "15_15") (pintype "passive"))
    )
    (net (code "329") (name "unconnected-(SV10-Pad16)") (class "Default")
      (node (ref "SV10") (pin "16") (pinfunction "16_16") (pintype "passive"))
    )
    (net (code "330") (name "unconnected-(SV10-Pad17)") (class "Default")
      (node (ref "SV10") (pin "17") (pinfunction "17_17") (pintype "passive"))
    )
    (net (code "331") (name "unconnected-(SV10-Pad18)") (class "Default")
      (node (ref "SV10") (pin "18") (pinfunction "18_18") (pintype "passive"))
    )
    (net (code "332") (name "unconnected-(SV10-Pad19)") (class "Default")
      (node (ref "SV10") (pin "19") (pinfunction "19_19") (pintype "passive"))
    )
    (net (code "333") (name "unconnected-(SV10-Pad20)") (class "Default")
      (node (ref "SV10") (pin "20") (pinfunction "20_20") (pintype "passive"))
    )
    (net (code "334") (name "unconnected-(SV11-Pad1)") (class "Default")
      (node (ref "SV11") (pin "1") (pinfunction "1_1") (pintype "passive"))
    )
    (net (code "335") (name "unconnected-(SV11-Pad2)") (class "Default")
      (node (ref "SV11") (pin "2") (pinfunction "2_2") (pintype "passive"))
    )
    (net (code "336") (name "unconnected-(SV11-Pad3)") (class "Default")
      (node (ref "SV11") (pin "3") (pinfunction "3_3") (pintype "passive"))
    )
    (net (code "337") (name "unconnected-(SV11-Pad4)") (class "Default")
      (node (ref "SV11") (pin "4") (pinfunction "4_4") (pintype "passive"))
    )
    (net (code "338") (name "unconnected-(SV11-Pad5)") (class "Default")
      (node (ref "SV11") (pin "5") (pinfunction "5_5") (pintype "passive"))
    )
    (net (code "339") (name "unconnected-(SV11-Pad6)") (class "Default")
      (node (ref "SV11") (pin "6") (pinfunction "6_6") (pintype "passive"))
    )
    (net (code "340") (name "unconnected-(SV11-Pad7)") (class "Default")
      (node (ref "SV11") (pin "7") (pinfunction "7_7") (pintype "passive"))
    )
    (net (code "341") (name "unconnected-(SV11-Pad8)") (class "Default")
      (node (ref "SV11") (pin "8") (pinfunction "8_8") (pintype "passive"))
    )
    (net (code "342") (name "unconnected-(SV11-Pad9)") (class "Default")
      (node (ref "SV11") (pin "9") (pinfunction "9_9") (pintype "passive"))
    )
    (net (code "343") (name "unconnected-(SV11-Pad10)") (class "Default")
      (node (ref "SV11") (pin "10") (pinfunction "10_10") (pintype "passive"))
    )
    (net (code "344") (name "unconnected-(SV11-Pad11)") (class "Default")
      (node (ref "SV11") (pin "11") (pinfunction "11_11") (pintype "passive"))
    )
    (net (code "345") (name "unconnected-(SV11-Pad12)") (class "Default")
      (node (ref "SV11") (pin "12") (pinfunction "12_12") (pintype "passive"))
    )
    (net (code "346") (name "unconnected-(SV11-Pad13)") (class "Default")
      (node (ref "SV11") (pin "13") (pinfunction "13_13") (pintype "passive"))
    )
    (net (code "347") (name "unconnected-(SV11-Pad14)") (class "Default")
      (node (ref "SV11") (pin "14") (pinfunction "14_14") (pintype "passive"))
    )
    (net (code "348") (name "unconnected-(SV11-Pad15)") (class "Default")
      (node (ref "SV11") (pin "15") (pinfunction "15_15") (pintype "passive"))
    )
    (net (code "349") (name "unconnected-(SV11-Pad16)") (class "Default")
      (node (ref "SV11") (pin "16") (pinfunction "16_16") (pintype "passive"))
    )
    (net (code "350") (name "unconnected-(SV11-Pad17)") (class "Default")
      (node (ref "SV11") (pin "17") (pinfunction "17_17") (pintype "passive"))
    )
    (net (code "351") (name "unconnected-(SV11-Pad18)") (class "Default")
      (node (ref "SV11") (pin "18") (pinfunction "18_18") (pintype "passive"))
    )
    (net (code "352") (name "unconnected-(SV11-Pad19)") (class "Default")
      (node (ref "SV11") (pin "19") (pinfunction "19_19") (pintype "passive"))
    )
    (net (code "353") (name "unconnected-(SV11-Pad20)") (class "Default")
      (node (ref "SV11") (pin "20") (pinfunction "20_20") (pintype "passive"))
    )
    (net (code "354") (name "unconnected-(U$1-Pad32KHZ)") (class "Default")
      (node (ref "U$1") (pin "32KHZ") (pinfunction "32KHZ_32KHZ") (pintype "output"))
    )
    (net (code "355") (name "unconnected-(U$1-~{RST}-Pad!RST)") (class "Default")
      (node (ref "U$1") (pin "!RST") (pinfunction "~{RST}_!RST") (pintype "bidirectional"))
    )
    (net (code "356") (name "unconnected-(U$3-+1-Pad+$2)") (class "Default")
      (node (ref "U$3") (pin "+$2") (pinfunction "+1_+$2") (pintype "passive"))
    )
    (net (code "357") (name "unconnected-(U$5-ANT_DET-PadP$62)") (class "Default")
      (node (ref "U$5") (pin "P$62") (pinfunction "ANT_DET_P$62") (pintype "input"))
    )
    (net (code "358") (name "unconnected-(U$5-CTS-PadP$11)") (class "Default")
      (node (ref "U$5") (pin "P$11") (pinfunction "CTS_P$11") (pintype "output"))
    )
    (net (code "359") (name "unconnected-(U$5-GPIO2-PadP$24)") (class "Default")
      (node (ref "U$5") (pin "P$24") (pinfunction "GPIO2_P$24") (pintype "bidirectional"))
    )
    (net (code "360") (name "unconnected-(U$5-RSVD-PadP$8)") (class "Default")
      (node (ref "U$5") (pin "P$8") (pinfunction "RSVD_P$8") (pintype "no_connect"))
    )
    (net (code "361") (name "unconnected-(U$5-SCL-PadP$27)") (class "Default")
      (node (ref "U$5") (pin "P$27") (pinfunction "SCL_P$27") (pintype "output"))
    )
    (net (code "362") (name "unconnected-(U$5-SDA-PadP$26)") (class "Default")
      (node (ref "U$5") (pin "P$26") (pinfunction "SDA_P$26") (pintype "bidirectional"))
    )
    (net (code "363") (name "unconnected-(U1-A2-PadP$3)") (class "Default")
      (node (ref "U1") (pin "P$3") (pinfunction "A2_P$3") (pintype "bidirectional"))
    )
    (net (code "364") (name "unconnected-(U1-A5-PadP$6)") (class "Default")
      (node (ref "U1") (pin "P$6") (pinfunction "A5_P$6") (pintype "bidirectional"))
    )
    (net (code "365") (name "unconnected-(U1-A6-PadP$7)") (class "Default")
      (node (ref "U1") (pin "P$7") (pinfunction "A6_P$7") (pintype "bidirectional"))
    )
    (net (code "366") (name "unconnected-(U1-B2-PadP$14)") (class "Default")
      (node (ref "U1") (pin "P$14") (pinfunction "B2_P$14") (pintype "bidirectional"))
    )
    (net (code "367") (name "unconnected-(U1-B5-PadP$11)") (class "Default")
      (node (ref "U1") (pin "P$11") (pinfunction "B5_P$11") (pintype "bidirectional"))
    )
    (net (code "368") (name "unconnected-(U1-B6-PadP$10)") (class "Default")
      (node (ref "U1") (pin "P$10") (pinfunction "B6_P$10") (pintype "bidirectional"))
    )
    (net (code "369") (name "unconnected-(U4-CLK-Pad20)") (class "Default")
      (node (ref "U4") (pin "20") (pinfunction "CLK_20") (pintype "bidirectional"))
    )
    (net (code "370") (name "unconnected-(U4-CMD-Pad19)") (class "Default")
      (node (ref "U4") (pin "19") (pinfunction "CMD_19") (pintype "bidirectional"))
    )
    (net (code "371") (name "unconnected-(U4-SD0-Pad21)") (class "Default")
      (node (ref "U4") (pin "21") (pinfunction "SD0_21") (pintype "bidirectional"))
    )
    (net (code "372") (name "unconnected-(U4-SD1-Pad22)") (class "Default")
      (node (ref "U4") (pin "22") (pinfunction "SD1_22") (pintype "bidirectional"))
    )
  )
)
